# axiom_beta_plugin_module_TE0714_SDI_v0_9.net
KiCad netlist of a schematic drawn in EAGLE
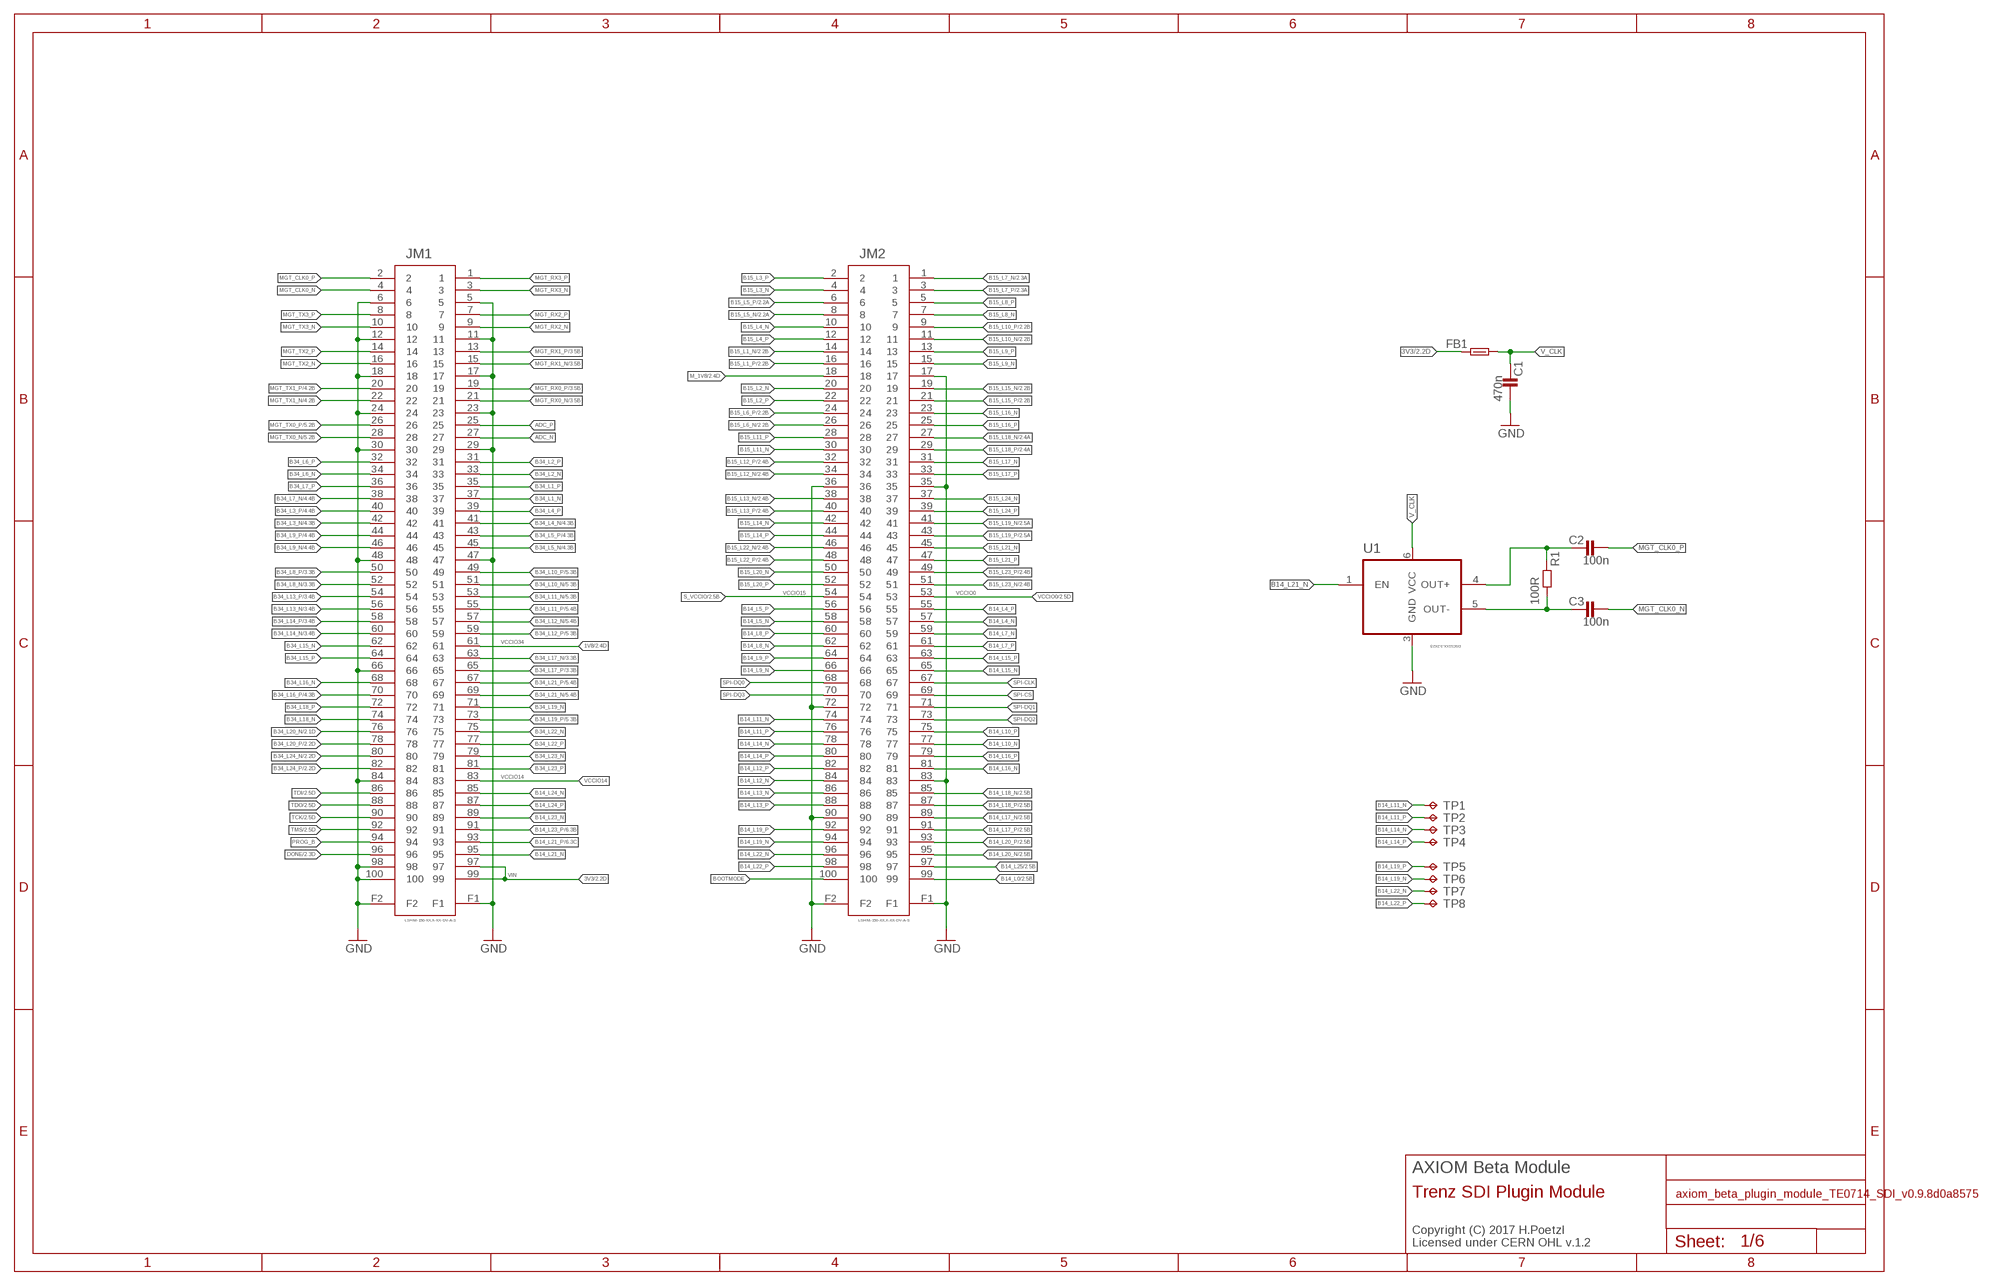
[diagram p0: schematic, sheet 1]
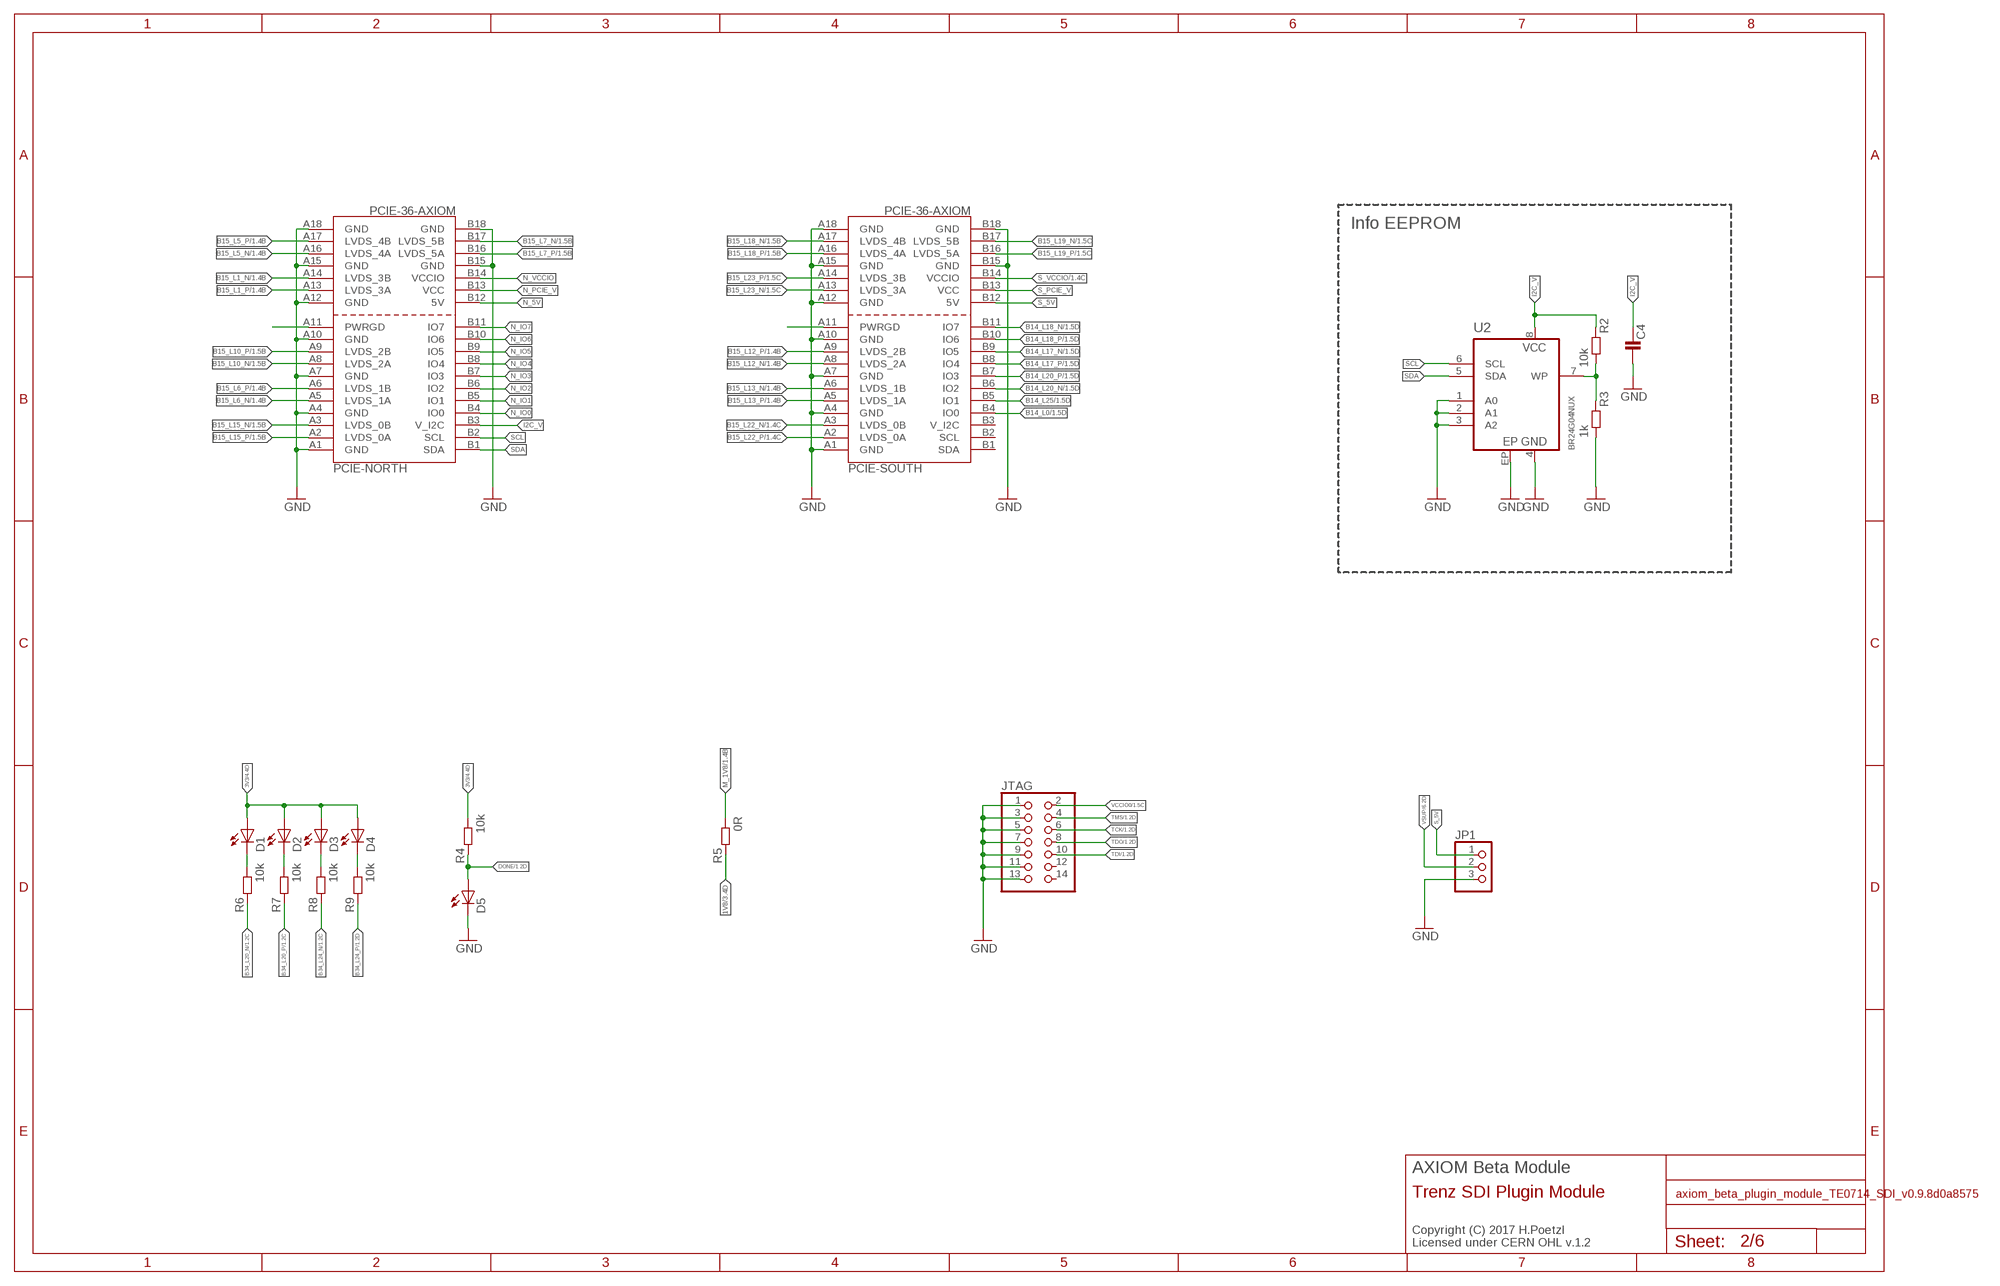
[diagram p1: schematic, sheet 2]
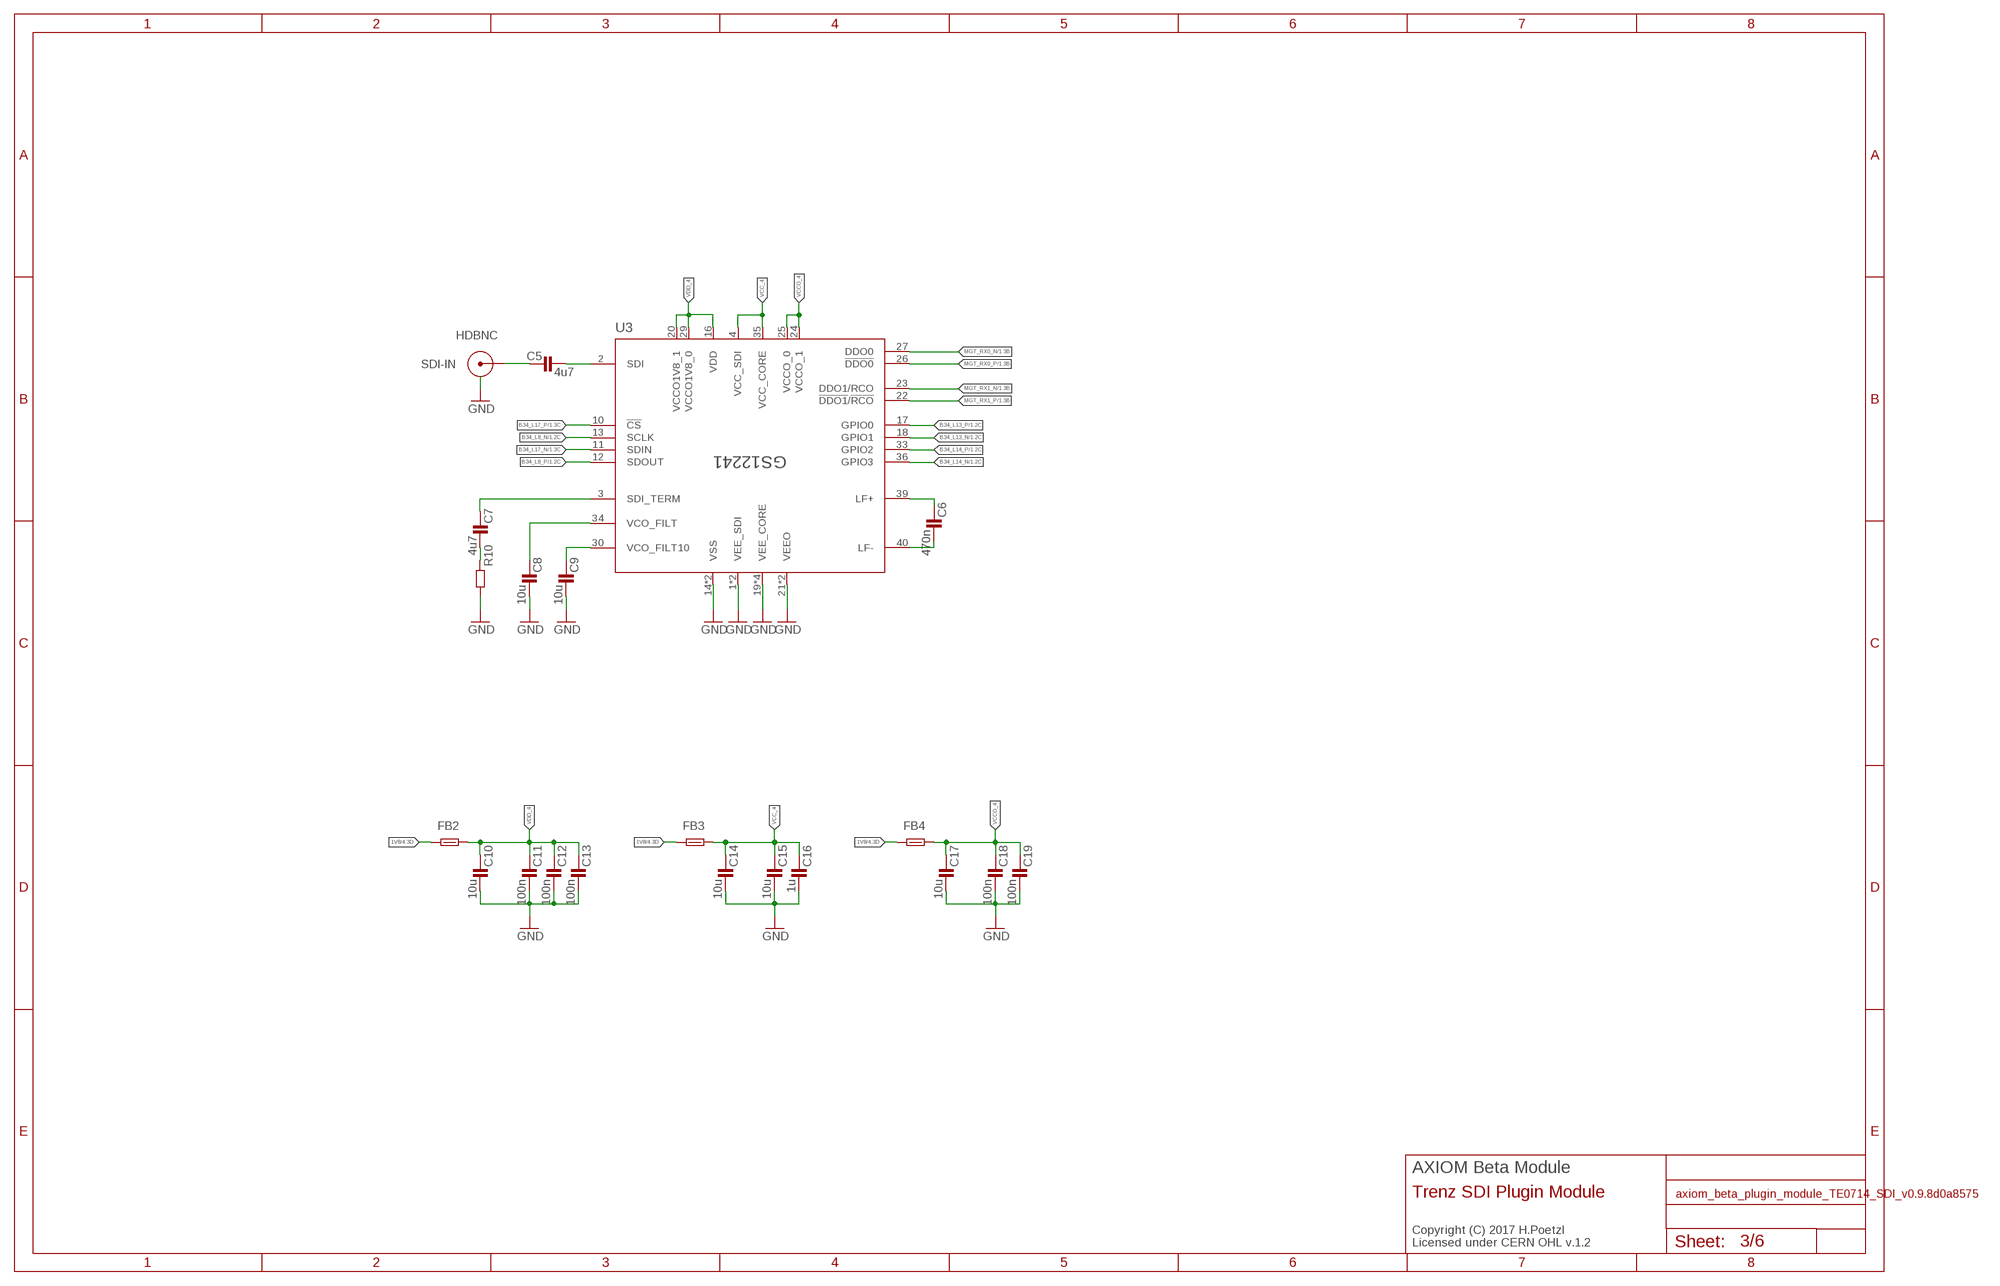
[diagram p2: schematic, sheet 3]
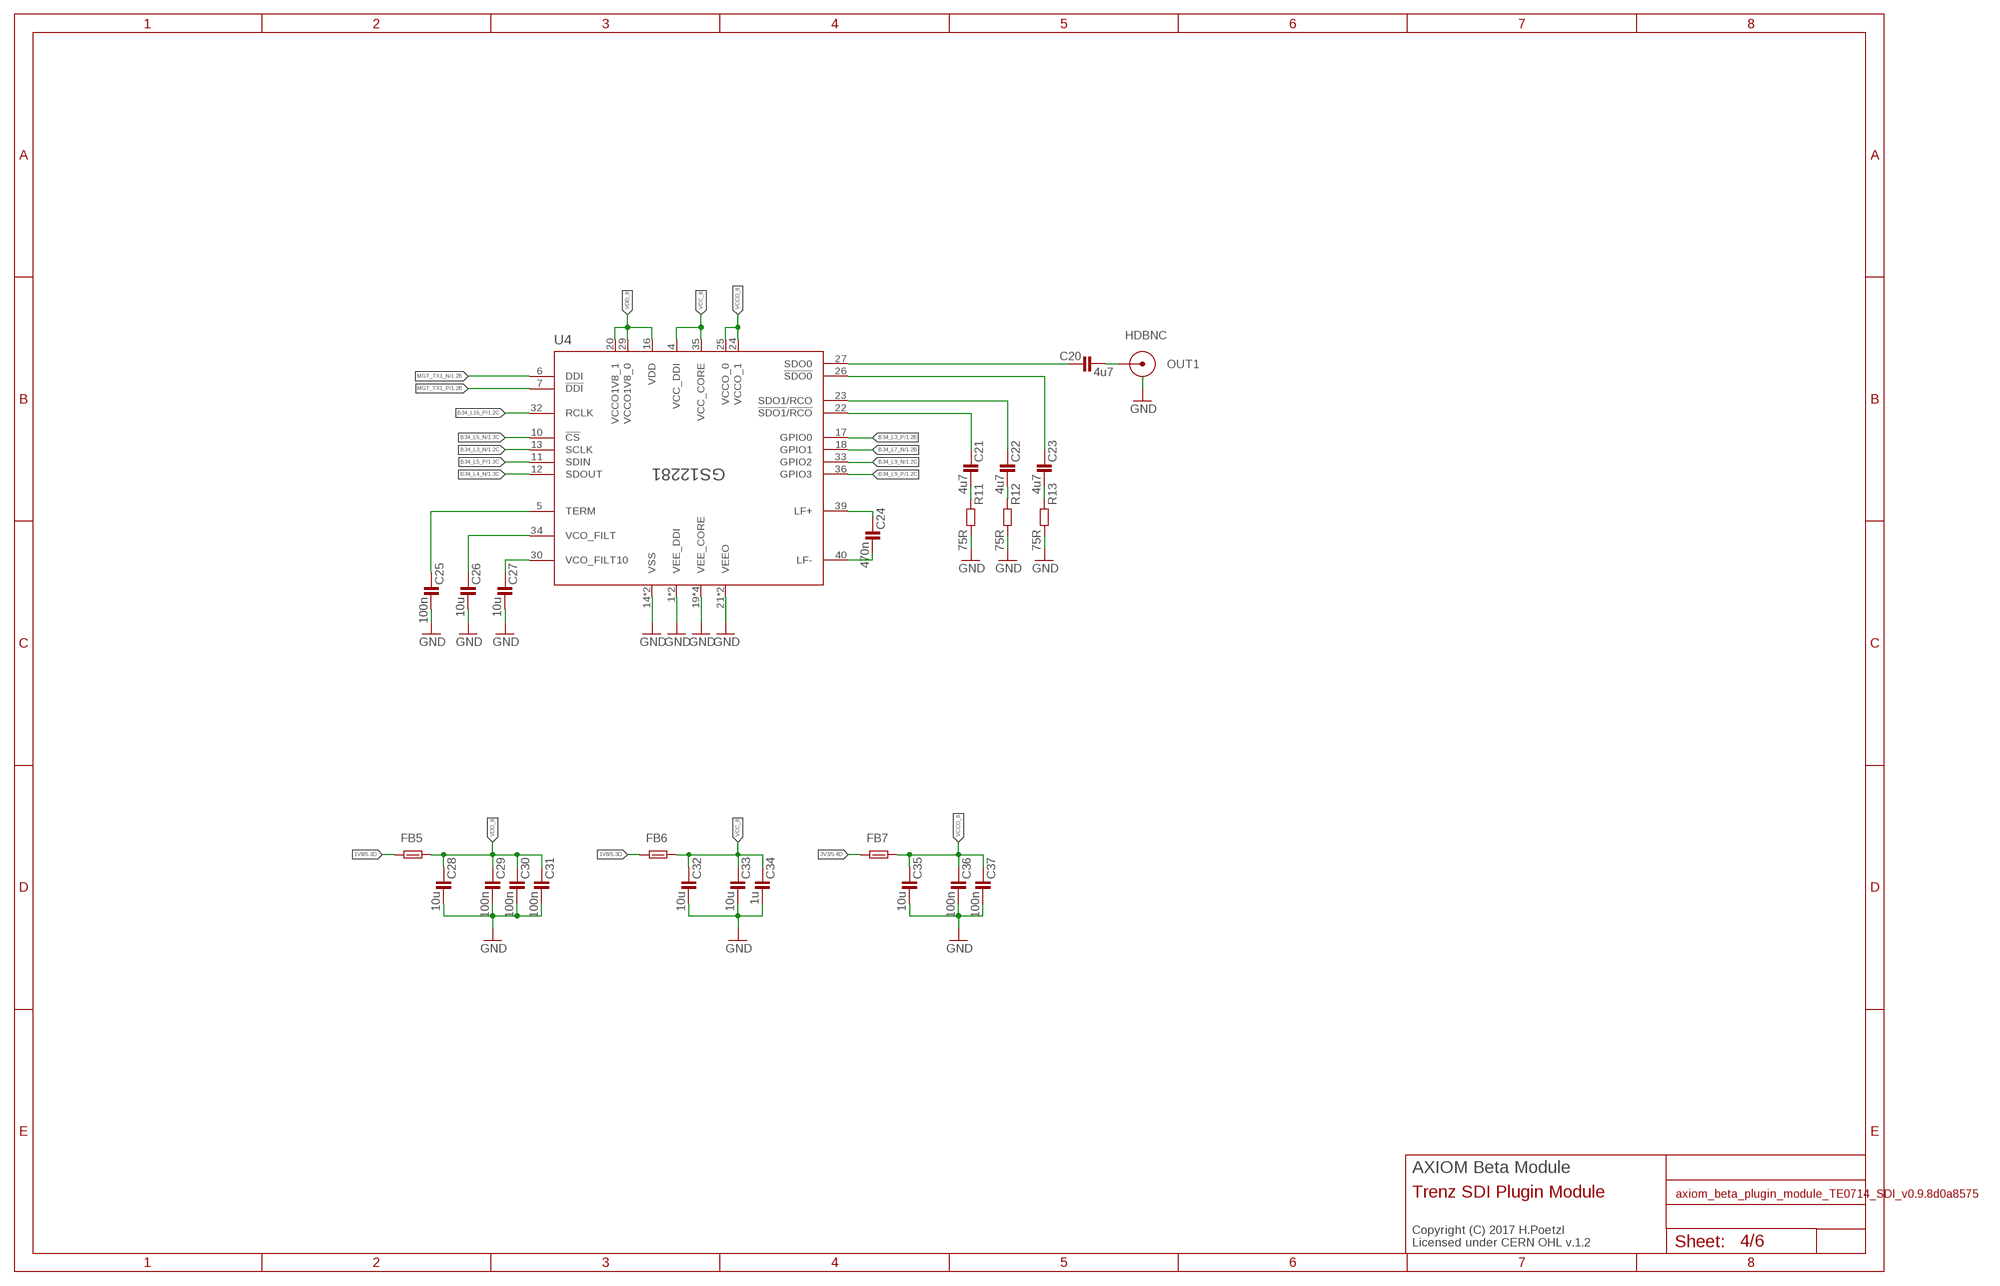
[diagram p3: schematic, sheet 4]
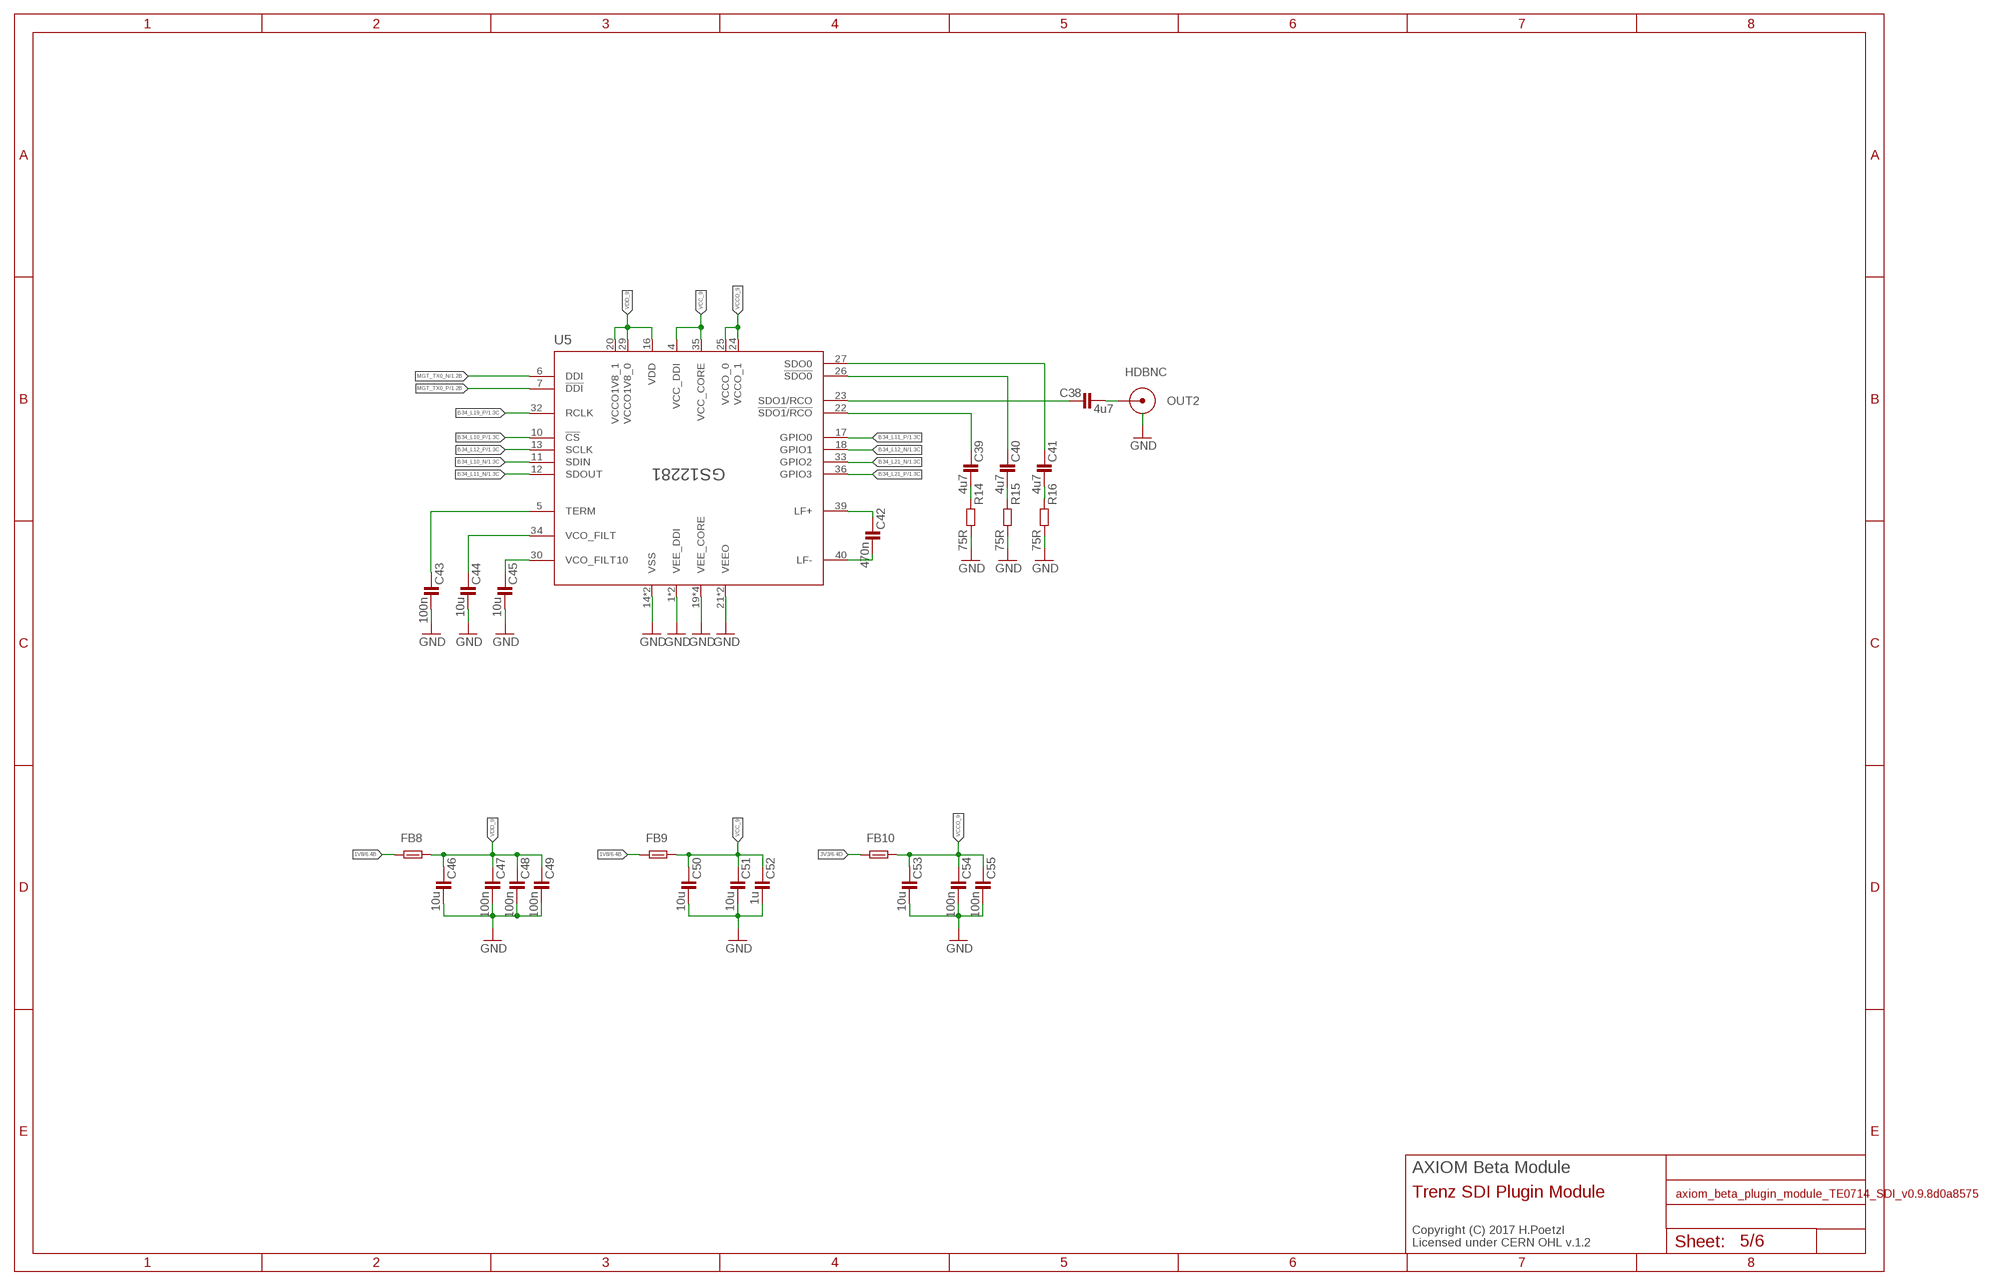
[diagram p4: schematic, sheet 5]
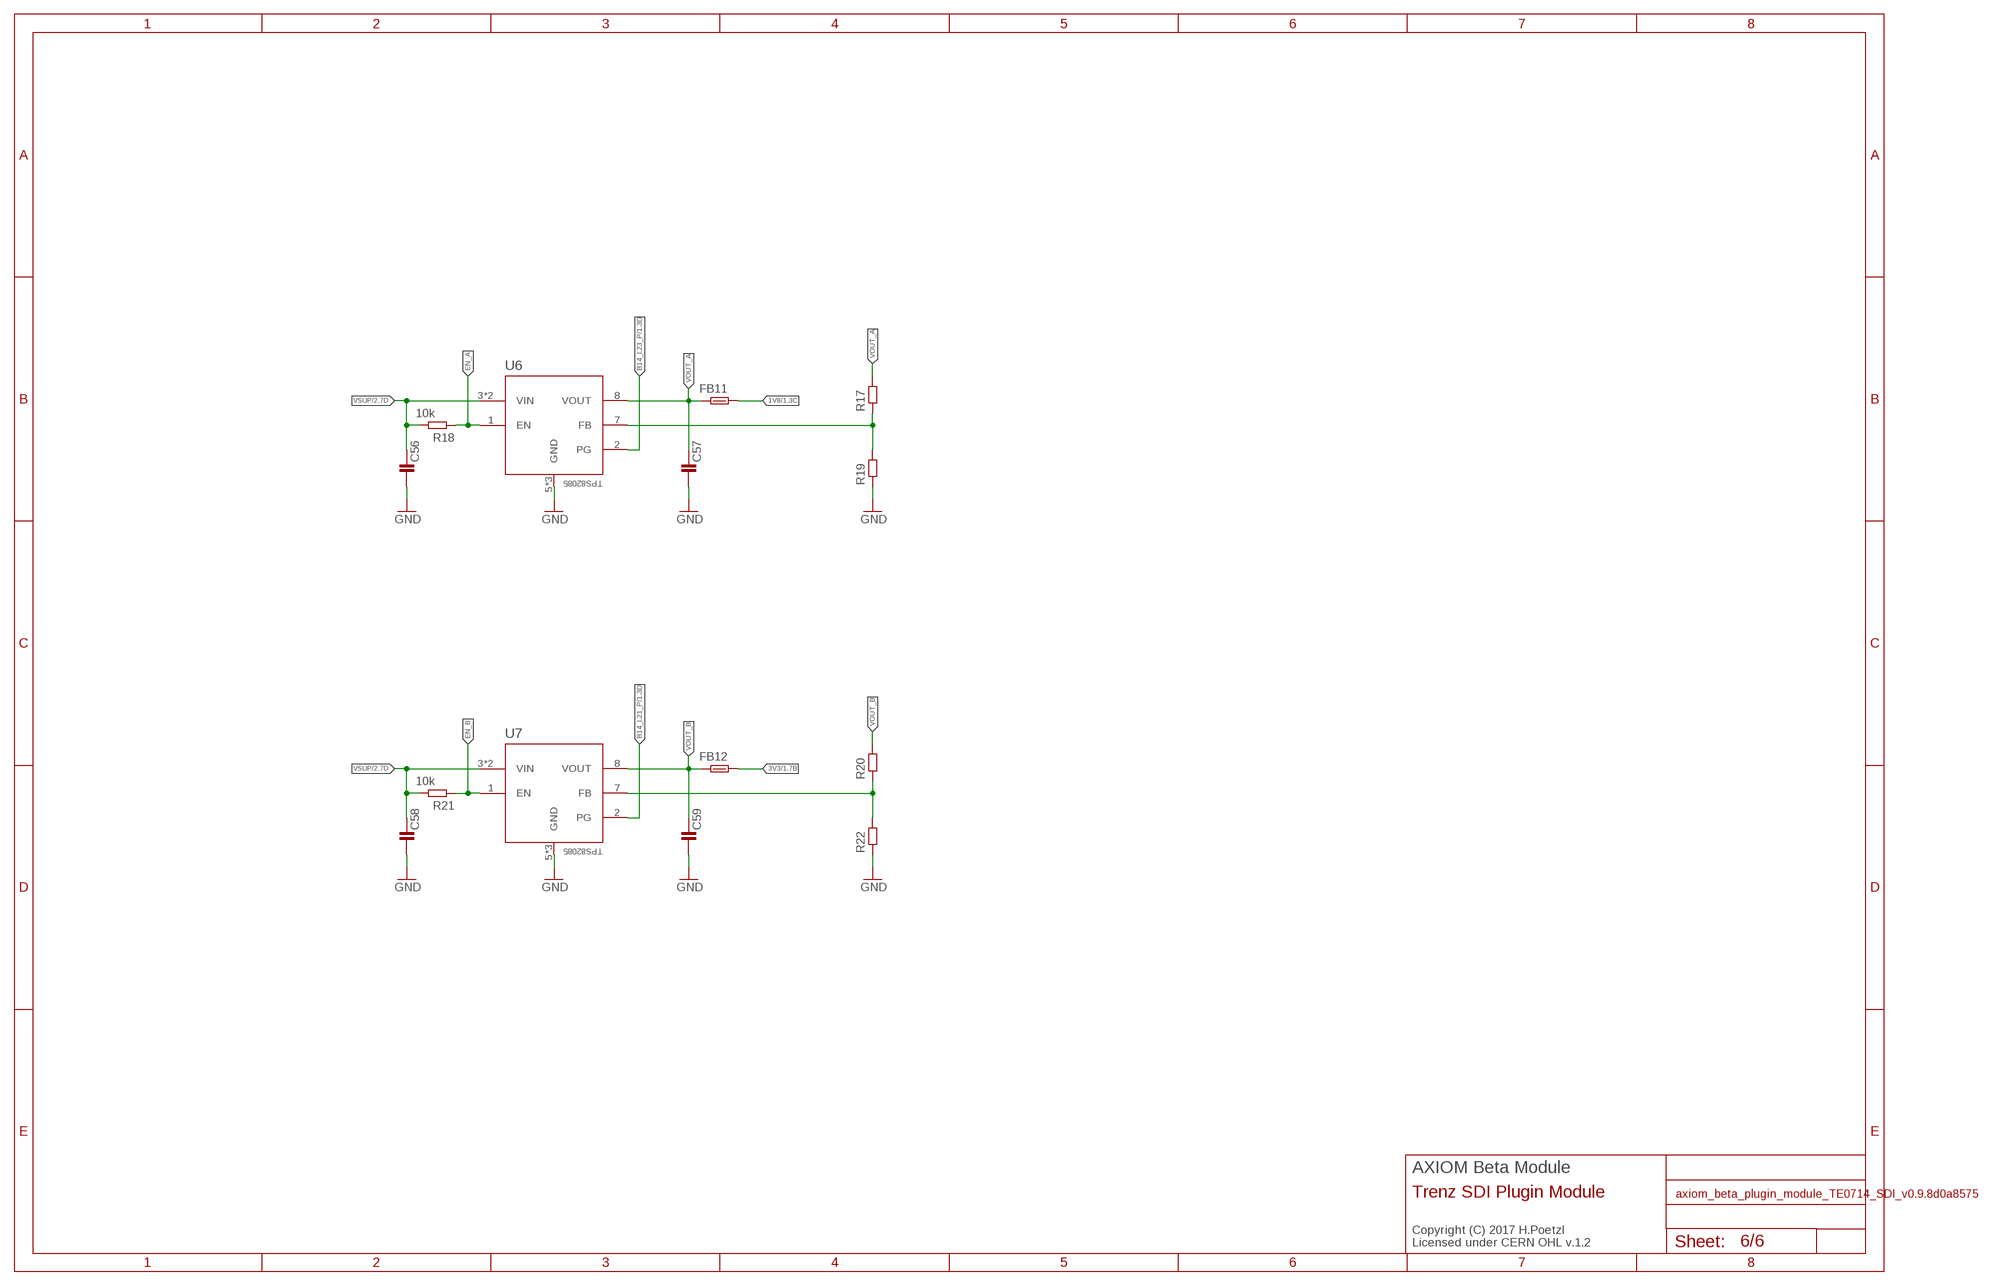
[diagram p5: schematic, sheet 6]

(export (version "E")
  (design (tool "Eeschema 10.0.6"))
  (components
    (comp (ref "C1")
      (value "470n")
      (footprint "eagle-import:0402-C")
      (libsource (lib "eagle-import") (part "C0402-C"))
    )
    (comp (ref "C2")
      (value "100n")
      (footprint "eagle-import:0201-C")
      (libsource (lib "eagle-import") (part "C0201-C"))
    )
    (comp (ref "C3")
      (value "100n")
      (footprint "eagle-import:0201-C")
      (libsource (lib "eagle-import") (part "C0201-C"))
    )
    (comp (ref "FB1")
      (value "FB0402-C")
      (footprint "eagle-import:0402-C")
      (libsource (lib "eagle-import") (part "FB0402-C"))
    )
    (comp (ref "JM1")
      (value "LSHM-150-XX.X-XX-DV-A-S")
      (footprint "eagle-import:LSHM-150-XX.X-XX-DV-A-S")
      (libsource (lib "eagle-import") (part "LSHM-150-XX.X-XX-DV-A-S"))
    )
    (comp (ref "JM2")
      (value "LSHM-150-XX.X-XX-DV-A-S")
      (footprint "eagle-import:LSHM-150-XX.X-XX-DV-A-S")
      (libsource (lib "eagle-import") (part "LSHM-150-XX.X-XX-DV-A-S"))
    )
    (comp (ref "R1")
      (value "100R")
      (footprint "eagle-import:0201-C")
      (libsource (lib "eagle-import") (part "R0201-C"))
    )
    (comp (ref "TP1")
      (value "TPTP08R")
      (footprint "eagle-import:TP08R")
      (libsource (lib "eagle-import") (part "TPTP08R"))
    )
    (comp (ref "TP2")
      (value "TPTP08R")
      (footprint "eagle-import:TP08R")
      (libsource (lib "eagle-import") (part "TPTP08R"))
    )
    (comp (ref "TP3")
      (value "TPTP08R")
      (footprint "eagle-import:TP08R")
      (libsource (lib "eagle-import") (part "TPTP08R"))
    )
    (comp (ref "TP4")
      (value "TPTP08R")
      (footprint "eagle-import:TP08R")
      (libsource (lib "eagle-import") (part "TPTP08R"))
    )
    (comp (ref "TP5")
      (value "TPTP10R")
      (footprint "eagle-import:TP10R")
      (libsource (lib "eagle-import") (part "TPTP10R"))
    )
    (comp (ref "TP6")
      (value "TPTP10R")
      (footprint "eagle-import:TP10R")
      (libsource (lib "eagle-import") (part "TPTP10R"))
    )
    (comp (ref "TP7")
      (value "TPTP10R")
      (footprint "eagle-import:TP10R")
      (libsource (lib "eagle-import") (part "TPTP10R"))
    )
    (comp (ref "TP8")
      (value "TPTP10R")
      (footprint "eagle-import:TP10R")
      (libsource (lib "eagle-import") (part "TPTP10R"))
    )
    (comp (ref "U1")
      (value "DSC11XX-3.2X2.5")
      (footprint "eagle-import:3.2X2.5")
      (libsource (lib "eagle-import") (part "DSC11XX-3.2X2.5"))
    )
    (comp (ref "C20")
      (value "4u7")
      (footprint "eagle-import:0402-C")
      (libsource (lib "eagle-import") (part "C0402-C"))
    )
    (comp (ref "C21")
      (value "4u7")
      (footprint "eagle-import:0402-C")
      (libsource (lib "eagle-import") (part "C0402-C"))
    )
    (comp (ref "C22")
      (value "4u7")
      (footprint "eagle-import:0402-C")
      (libsource (lib "eagle-import") (part "C0402-C"))
    )
    (comp (ref "C23")
      (value "4u7")
      (footprint "eagle-import:0402-C")
      (libsource (lib "eagle-import") (part "C0402-C"))
    )
    (comp (ref "C24")
      (value "470n")
      (footprint "eagle-import:0201-C")
      (libsource (lib "eagle-import") (part "C0201-C"))
    )
    (comp (ref "C25")
      (value "100n")
      (footprint "eagle-import:0201-C")
      (libsource (lib "eagle-import") (part "C0201-C"))
    )
    (comp (ref "C26")
      (value "10u")
      (footprint "eagle-import:0201-C")
      (libsource (lib "eagle-import") (part "C0201-C"))
    )
    (comp (ref "C27")
      (value "10u")
      (footprint "eagle-import:0402-C")
      (libsource (lib "eagle-import") (part "C0402-C"))
    )
    (comp (ref "C28")
      (value "10u")
      (footprint "eagle-import:0402-C")
      (libsource (lib "eagle-import") (part "C0402-C"))
    )
    (comp (ref "C29")
      (value "100n")
      (footprint "eagle-import:0201-C")
      (libsource (lib "eagle-import") (part "C0201-C"))
    )
    (comp (ref "C30")
      (value "100n")
      (footprint "eagle-import:0201-C")
      (libsource (lib "eagle-import") (part "C0201-C"))
    )
    (comp (ref "C31")
      (value "100n")
      (footprint "eagle-import:0201-C")
      (libsource (lib "eagle-import") (part "C0201-C"))
    )
    (comp (ref "C32")
      (value "10u")
      (footprint "eagle-import:0402-C")
      (libsource (lib "eagle-import") (part "C0402-C"))
    )
    (comp (ref "C33")
      (value "10u")
      (footprint "eagle-import:0402-C")
      (libsource (lib "eagle-import") (part "C0402-C"))
    )
    (comp (ref "C34")
      (value "1u")
      (footprint "eagle-import:0201-C")
      (libsource (lib "eagle-import") (part "C0201-C"))
    )
    (comp (ref "C35")
      (value "10u")
      (footprint "eagle-import:0402-C")
      (libsource (lib "eagle-import") (part "C0402-C"))
    )
    (comp (ref "C36")
      (value "100n")
      (footprint "eagle-import:0201-C")
      (libsource (lib "eagle-import") (part "C0201-C"))
    )
    (comp (ref "C37")
      (value "100n")
      (footprint "eagle-import:0201-C")
      (libsource (lib "eagle-import") (part "C0201-C"))
    )
    (comp (ref "FB5")
      (value "FB0402-C")
      (footprint "eagle-import:0402-C")
      (libsource (lib "eagle-import") (part "FB0402-C"))
    )
    (comp (ref "FB6")
      (value "FB0402-C")
      (footprint "eagle-import:0402-C")
      (libsource (lib "eagle-import") (part "FB0402-C"))
    )
    (comp (ref "FB7")
      (value "FB0402-C")
      (footprint "eagle-import:0402-C")
      (libsource (lib "eagle-import") (part "FB0402-C"))
    )
    (comp (ref "OUT1")
      (value "HDBNC")
      (footprint "eagle-import:HDBNC_EDGE_2SIDE")
      (libsource (lib "eagle-import") (part "HDBNC"))
    )
    (comp (ref "R11")
      (value "75R")
      (footprint "eagle-import:0201-C")
      (libsource (lib "eagle-import") (part "R0201-C"))
    )
    (comp (ref "R12")
      (value "75R")
      (footprint "eagle-import:0201-C")
      (libsource (lib "eagle-import") (part "R0201-C"))
    )
    (comp (ref "R13")
      (value "75R")
      (footprint "eagle-import:0201-C")
      (libsource (lib "eagle-import") (part "R0201-C"))
    )
    (comp (ref "U4")
      (value "GS12281")
      (footprint "eagle-import:UQFN40P600X400X100-41N")
      (libsource (lib "eagle-import") (part "GS12281"))
    )
    (comp (ref "C4")
      (value "C0402-B")
      (footprint "eagle-import:0402-B")
      (libsource (lib "eagle-import") (part "C0402-B"))
    )
    (comp (ref "D1")
      (value "LED")
      (footprint "eagle-import:CHIPLED_0603")
      (libsource (lib "eagle-import") (part "LED"))
    )
    (comp (ref "D2")
      (value "LED")
      (footprint "eagle-import:CHIPLED_0603")
      (libsource (lib "eagle-import") (part "LED"))
    )
    (comp (ref "D3")
      (value "LED")
      (footprint "eagle-import:CHIPLED_0603")
      (libsource (lib "eagle-import") (part "LED"))
    )
    (comp (ref "D4")
      (value "LED")
      (footprint "eagle-import:CHIPLED_0603")
      (libsource (lib "eagle-import") (part "LED"))
    )
    (comp (ref "D5")
      (value "LED")
      (footprint "eagle-import:CHIPLED_0603")
      (libsource (lib "eagle-import") (part "LED"))
    )
    (comp (ref "JP1")
      (value "PINHD-1X03_2.54-90°-S")
      (footprint "eagle-import:1X03_90-S")
      (libsource (lib "eagle-import") (part "PINHD-1X03_2.54-90°-S"))
    )
    (comp (ref "JTAG")
      (value "PINHD-2X07_2.00")
      (footprint "eagle-import:2X07M")
      (libsource (lib "eagle-import") (part "PINHD-2X07_2.00"))
    )
    (comp (ref "PCIE-NORTH")
      (value "PCIE-36-AXIOM")
      (footprint "eagle-import:PCIE-36-AXIOM")
      (libsource (lib "eagle-import") (part "PCIE-36-AXIOM"))
    )
    (comp (ref "PCIE-SOUTH")
      (value "PCIE-36-AXIOM")
      (footprint "eagle-import:PCIE-36-AXIOM")
      (libsource (lib "eagle-import") (part "PCIE-36-AXIOM"))
    )
    (comp (ref "R2")
      (value "10k")
      (footprint "eagle-import:0402-B")
      (libsource (lib "eagle-import") (part "R0402-B"))
    )
    (comp (ref "R3")
      (value "1k")
      (footprint "eagle-import:0402-B")
      (libsource (lib "eagle-import") (part "R0402-B"))
    )
    (comp (ref "R4")
      (value "10k")
      (footprint "eagle-import:0402-C")
      (libsource (lib "eagle-import") (part "R0402-C"))
    )
    (comp (ref "R5")
      (value "0R")
      (footprint "eagle-import:0402-C")
      (libsource (lib "eagle-import") (part "R0402-C"))
    )
    (comp (ref "R6")
      (value "10k")
      (footprint "eagle-import:0402-C")
      (libsource (lib "eagle-import") (part "R0402-C"))
    )
    (comp (ref "R7")
      (value "10k")
      (footprint "eagle-import:0402-C")
      (libsource (lib "eagle-import") (part "R0402-C"))
    )
    (comp (ref "R8")
      (value "10k")
      (footprint "eagle-import:0402-C")
      (libsource (lib "eagle-import") (part "R0402-C"))
    )
    (comp (ref "R9")
      (value "10k")
      (footprint "eagle-import:0402-C")
      (libsource (lib "eagle-import") (part "R0402-C"))
    )
    (comp (ref "U2")
      (value "BR24G04NUX")
      (footprint "eagle-import:DFN200X300X100-9N")
      (libsource (lib "eagle-import") (part "BR24G04NUX"))
    )
    (comp (ref "C5")
      (value "4u7")
      (footprint "eagle-import:0402-C")
      (libsource (lib "eagle-import") (part "C0402-C"))
    )
    (comp (ref "C6")
      (value "470n")
      (footprint "eagle-import:0201-C")
      (libsource (lib "eagle-import") (part "C0201-C"))
    )
    (comp (ref "C7")
      (value "4u7")
      (footprint "eagle-import:0402-C")
      (libsource (lib "eagle-import") (part "C0402-C"))
    )
    (comp (ref "C8")
      (value "10u")
      (footprint "eagle-import:0201-C")
      (libsource (lib "eagle-import") (part "C0201-C"))
    )
    (comp (ref "C9")
      (value "10u")
      (footprint "eagle-import:0402-C")
      (libsource (lib "eagle-import") (part "C0402-C"))
    )
    (comp (ref "C10")
      (value "10u")
      (footprint "eagle-import:0402-C")
      (libsource (lib "eagle-import") (part "C0402-C"))
    )
    (comp (ref "C11")
      (value "100n")
      (footprint "eagle-import:0201-C")
      (libsource (lib "eagle-import") (part "C0201-C"))
    )
    (comp (ref "C12")
      (value "100n")
      (footprint "eagle-import:0201-C")
      (libsource (lib "eagle-import") (part "C0201-C"))
    )
    (comp (ref "C13")
      (value "100n")
      (footprint "eagle-import:0201-C")
      (libsource (lib "eagle-import") (part "C0201-C"))
    )
    (comp (ref "C14")
      (value "10u")
      (footprint "eagle-import:0402-C")
      (libsource (lib "eagle-import") (part "C0402-C"))
    )
    (comp (ref "C15")
      (value "10u")
      (footprint "eagle-import:0402-C")
      (libsource (lib "eagle-import") (part "C0402-C"))
    )
    (comp (ref "C16")
      (value "1u")
      (footprint "eagle-import:0201-C")
      (libsource (lib "eagle-import") (part "C0201-C"))
    )
    (comp (ref "C17")
      (value "10u")
      (footprint "eagle-import:0402-C")
      (libsource (lib "eagle-import") (part "C0402-C"))
    )
    (comp (ref "C18")
      (value "100n")
      (footprint "eagle-import:0201-C")
      (libsource (lib "eagle-import") (part "C0201-C"))
    )
    (comp (ref "C19")
      (value "100n")
      (footprint "eagle-import:0201-C")
      (libsource (lib "eagle-import") (part "C0201-C"))
    )
    (comp (ref "FB2")
      (value "FB0402-C")
      (footprint "eagle-import:0402-C")
      (libsource (lib "eagle-import") (part "FB0402-C"))
    )
    (comp (ref "FB3")
      (value "FB0402-C")
      (footprint "eagle-import:0402-C")
      (libsource (lib "eagle-import") (part "FB0402-C"))
    )
    (comp (ref "FB4")
      (value "FB0402-C")
      (footprint "eagle-import:0402-C")
      (libsource (lib "eagle-import") (part "FB0402-C"))
    )
    (comp (ref "R10")
      (value "R0201-C")
      (footprint "eagle-import:0201-C")
      (libsource (lib "eagle-import") (part "R0201-C"))
    )
    (comp (ref "SDI-IN")
      (value "HDBNC")
      (footprint "eagle-import:HDBNC_EDGE_2SIDE")
      (libsource (lib "eagle-import") (part "HDBNC"))
    )
    (comp (ref "U3")
      (value "GS12241")
      (footprint "eagle-import:UQFN40P600X400X100-41N")
      (libsource (lib "eagle-import") (part "GS12241"))
    )
    (comp (ref "C38")
      (value "4u7")
      (footprint "eagle-import:0402-C")
      (libsource (lib "eagle-import") (part "C0402-C"))
    )
    (comp (ref "C39")
      (value "4u7")
      (footprint "eagle-import:0402-C")
      (libsource (lib "eagle-import") (part "C0402-C"))
    )
    (comp (ref "C40")
      (value "4u7")
      (footprint "eagle-import:0402-C")
      (libsource (lib "eagle-import") (part "C0402-C"))
    )
    (comp (ref "C41")
      (value "4u7")
      (footprint "eagle-import:0402-C")
      (libsource (lib "eagle-import") (part "C0402-C"))
    )
    (comp (ref "C42")
      (value "470n")
      (footprint "eagle-import:0201-C")
      (libsource (lib "eagle-import") (part "C0201-C"))
    )
    (comp (ref "C43")
      (value "100n")
      (footprint "eagle-import:0201-C")
      (libsource (lib "eagle-import") (part "C0201-C"))
    )
    (comp (ref "C44")
      (value "10u")
      (footprint "eagle-import:0402-C")
      (libsource (lib "eagle-import") (part "C0402-C"))
    )
    (comp (ref "C45")
      (value "10u")
      (footprint "eagle-import:0402-C")
      (libsource (lib "eagle-import") (part "C0402-C"))
    )
    (comp (ref "C46")
      (value "10u")
      (footprint "eagle-import:0402-C")
      (libsource (lib "eagle-import") (part "C0402-C"))
    )
    (comp (ref "C47")
      (value "100n")
      (footprint "eagle-import:0201-C")
      (libsource (lib "eagle-import") (part "C0201-C"))
    )
    (comp (ref "C48")
      (value "100n")
      (footprint "eagle-import:0201-C")
      (libsource (lib "eagle-import") (part "C0201-C"))
    )
    (comp (ref "C49")
      (value "100n")
      (footprint "eagle-import:0201-C")
      (libsource (lib "eagle-import") (part "C0201-C"))
    )
    (comp (ref "C50")
      (value "10u")
      (footprint "eagle-import:0402-C")
      (libsource (lib "eagle-import") (part "C0402-C"))
    )
    (comp (ref "C51")
      (value "10u")
      (footprint "eagle-import:0402-C")
      (libsource (lib "eagle-import") (part "C0402-C"))
    )
    (comp (ref "C52")
      (value "1u")
      (footprint "eagle-import:0201-C")
      (libsource (lib "eagle-import") (part "C0201-C"))
    )
    (comp (ref "C53")
      (value "10u")
      (footprint "eagle-import:0402-C")
      (libsource (lib "eagle-import") (part "C0402-C"))
    )
    (comp (ref "C54")
      (value "100n")
      (footprint "eagle-import:0201-C")
      (libsource (lib "eagle-import") (part "C0201-C"))
    )
    (comp (ref "C55")
      (value "100n")
      (footprint "eagle-import:0201-C")
      (libsource (lib "eagle-import") (part "C0201-C"))
    )
    (comp (ref "FB8")
      (value "FB0402-C")
      (footprint "eagle-import:0402-C")
      (libsource (lib "eagle-import") (part "FB0402-C"))
    )
    (comp (ref "FB9")
      (value "FB0402-C")
      (footprint "eagle-import:0402-C")
      (libsource (lib "eagle-import") (part "FB0402-C"))
    )
    (comp (ref "FB10")
      (value "FB0402-C")
      (footprint "eagle-import:0402-C")
      (libsource (lib "eagle-import") (part "FB0402-C"))
    )
    (comp (ref "OUT2")
      (value "HDBNC")
      (footprint "eagle-import:HDBNC_EDGE_2SIDE")
      (libsource (lib "eagle-import") (part "HDBNC"))
    )
    (comp (ref "R14")
      (value "75R")
      (footprint "eagle-import:0201-C")
      (libsource (lib "eagle-import") (part "R0201-C"))
    )
    (comp (ref "R15")
      (value "75R")
      (footprint "eagle-import:0201-C")
      (libsource (lib "eagle-import") (part "R0201-C"))
    )
    (comp (ref "R16")
      (value "75R")
      (footprint "eagle-import:0201-C")
      (libsource (lib "eagle-import") (part "R0201-C"))
    )
    (comp (ref "U5")
      (value "GS12281")
      (footprint "eagle-import:UQFN40P600X400X100-41N")
      (libsource (lib "eagle-import") (part "GS12281"))
    )
    (comp (ref "C56")
      (value "C0603-C")
      (footprint "eagle-import:0603-C")
      (libsource (lib "eagle-import") (part "C0603-C"))
    )
    (comp (ref "C57")
      (value "C0603-C")
      (footprint "eagle-import:0603-C")
      (libsource (lib "eagle-import") (part "C0603-C"))
    )
    (comp (ref "C58")
      (value "C0603-C")
      (footprint "eagle-import:0603-C")
      (libsource (lib "eagle-import") (part "C0603-C"))
    )
    (comp (ref "C59")
      (value "C0603-C")
      (footprint "eagle-import:0603-C")
      (libsource (lib "eagle-import") (part "C0603-C"))
    )
    (comp (ref "FB11")
      (value "FB0603-C")
      (footprint "eagle-import:0603-C")
      (libsource (lib "eagle-import") (part "FB0603-C"))
    )
    (comp (ref "FB12")
      (value "FB0603-C")
      (footprint "eagle-import:0603-C")
      (libsource (lib "eagle-import") (part "FB0603-C"))
    )
    (comp (ref "R17")
      (value "R0201-C")
      (footprint "eagle-import:0201-C")
      (libsource (lib "eagle-import") (part "R0201-C"))
    )
    (comp (ref "R18")
      (value "10k")
      (footprint "eagle-import:0201-C")
      (libsource (lib "eagle-import") (part "R0201-C"))
    )
    (comp (ref "R19")
      (value "R0201-C")
      (footprint "eagle-import:0201-C")
      (libsource (lib "eagle-import") (part "R0201-C"))
    )
    (comp (ref "R20")
      (value "R0201-C")
      (footprint "eagle-import:0201-C")
      (libsource (lib "eagle-import") (part "R0201-C"))
    )
    (comp (ref "R21")
      (value "10k")
      (footprint "eagle-import:0201-C")
      (libsource (lib "eagle-import") (part "R0201-C"))
    )
    (comp (ref "R22")
      (value "R0201-C")
      (footprint "eagle-import:0201-C")
      (libsource (lib "eagle-import") (part "R0201-C"))
    )
    (comp (ref "U6")
      (value "TPS82085")
      (footprint "eagle-import:MICROSIP")
      (libsource (lib "eagle-import") (part "TPS82085"))
    )
    (comp (ref "U7")
      (value "TPS82085")
      (footprint "eagle-import:MICROSIP")
      (libsource (lib "eagle-import") (part "TPS82085"))
    )
  )
  (nets
    (net (code "1") (name "1V8") (class "Default")
      (node (ref "FB11") (pin "2") (pinfunction "2_2") (pintype "passive"))
      (node (ref "FB2") (pin "1") (pinfunction "1_1") (pintype "passive"))
      (node (ref "FB3") (pin "1") (pinfunction "1_1") (pintype "passive"))
      (node (ref "FB4") (pin "1") (pinfunction "1_1") (pintype "passive"))
      (node (ref "FB5") (pin "1") (pinfunction "1_1") (pintype "passive"))
      (node (ref "FB6") (pin "1") (pinfunction "1_1") (pintype "passive"))
      (node (ref "FB8") (pin "1") (pinfunction "1_1") (pintype "passive"))
      (node (ref "FB9") (pin "1") (pinfunction "1_1") (pintype "passive"))
      (node (ref "JM1") (pin "61") (pinfunction "61_61") (pintype "bidirectional"))
      (node (ref "R5") (pin "1") (pinfunction "1_1") (pintype "passive"))
    )
    (net (code "2") (name "3V3") (class "Default")
      (node (ref "D1") (pin "A") (pinfunction "A_A") (pintype "passive"))
      (node (ref "D2") (pin "A") (pinfunction "A_A") (pintype "passive"))
      (node (ref "D3") (pin "A") (pinfunction "A_A") (pintype "passive"))
      (node (ref "D4") (pin "A") (pinfunction "A_A") (pintype "passive"))
      (node (ref "FB1") (pin "1") (pinfunction "1_1") (pintype "passive"))
      (node (ref "FB10") (pin "1") (pinfunction "1_1") (pintype "passive"))
      (node (ref "FB12") (pin "2") (pinfunction "2_2") (pintype "passive"))
      (node (ref "FB7") (pin "1") (pinfunction "1_1") (pintype "passive"))
      (node (ref "JM1") (pin "97") (pinfunction "97_97") (pintype "bidirectional"))
      (node (ref "JM1") (pin "99") (pinfunction "99_99") (pintype "bidirectional"))
      (node (ref "R4") (pin "2") (pinfunction "2_2") (pintype "passive"))
    )
    (net (code "3") (name "ADC_N") (class "Default")
      (node (ref "JM1") (pin "27") (pinfunction "27_27") (pintype "bidirectional"))
    )
    (net (code "4") (name "ADC_P") (class "Default")
      (node (ref "JM1") (pin "25") (pinfunction "25_25") (pintype "bidirectional"))
    )
    (net (code "5") (name "B14_L0") (class "Default")
      (node (ref "JM2") (pin "99") (pinfunction "99_99") (pintype "bidirectional"))
      (node (ref "PCIE-SOUTH") (pin "B4") (pinfunction "IO0_B4") (pintype "passive"))
    )
    (net (code "6") (name "B14_L4_N") (class "Default")
      (node (ref "JM2") (pin "57") (pinfunction "57_57") (pintype "bidirectional"))
    )
    (net (code "7") (name "B14_L4_P") (class "Default")
      (node (ref "JM2") (pin "55") (pinfunction "55_55") (pintype "bidirectional"))
    )
    (net (code "8") (name "B14_L5_N") (class "Default")
      (node (ref "JM2") (pin "58") (pinfunction "58_58") (pintype "bidirectional"))
    )
    (net (code "9") (name "B14_L5_P") (class "Default")
      (node (ref "JM2") (pin "56") (pinfunction "56_56") (pintype "bidirectional"))
    )
    (net (code "10") (name "B14_L7_N") (class "Default")
      (node (ref "JM2") (pin "59") (pinfunction "59_59") (pintype "bidirectional"))
    )
    (net (code "11") (name "B14_L7_P") (class "Default")
      (node (ref "JM2") (pin "61") (pinfunction "61_61") (pintype "bidirectional"))
    )
    (net (code "12") (name "B14_L8_N") (class "Default")
      (node (ref "JM2") (pin "62") (pinfunction "62_62") (pintype "bidirectional"))
    )
    (net (code "13") (name "B14_L8_P") (class "Default")
      (node (ref "JM2") (pin "60") (pinfunction "60_60") (pintype "bidirectional"))
    )
    (net (code "14") (name "B14_L9_N") (class "Default")
      (node (ref "JM2") (pin "66") (pinfunction "66_66") (pintype "bidirectional"))
    )
    (net (code "15") (name "B14_L9_P") (class "Default")
      (node (ref "JM2") (pin "64") (pinfunction "64_64") (pintype "bidirectional"))
    )
    (net (code "16") (name "B14_L10_N") (class "Default")
      (node (ref "JM2") (pin "77") (pinfunction "77_77") (pintype "bidirectional"))
    )
    (net (code "17") (name "B14_L10_P") (class "Default")
      (node (ref "JM2") (pin "75") (pinfunction "75_75") (pintype "bidirectional"))
    )
    (net (code "18") (name "B14_L11_N") (class "Default")
      (node (ref "JM2") (pin "74") (pinfunction "74_74") (pintype "bidirectional"))
      (node (ref "TP1") (pin "TP") (pinfunction "TP_TP") (pintype "input"))
    )
    (net (code "19") (name "B14_L11_P") (class "Default")
      (node (ref "JM2") (pin "76") (pinfunction "76_76") (pintype "bidirectional"))
      (node (ref "TP2") (pin "TP") (pinfunction "TP_TP") (pintype "input"))
    )
    (net (code "20") (name "B14_L12_N") (class "Default")
      (node (ref "JM2") (pin "84") (pinfunction "84_84") (pintype "bidirectional"))
    )
    (net (code "21") (name "B14_L12_P") (class "Default")
      (node (ref "JM2") (pin "82") (pinfunction "82_82") (pintype "bidirectional"))
    )
    (net (code "22") (name "B14_L13_N") (class "Default")
      (node (ref "JM2") (pin "86") (pinfunction "86_86") (pintype "bidirectional"))
    )
    (net (code "23") (name "B14_L13_P") (class "Default")
      (node (ref "JM2") (pin "88") (pinfunction "88_88") (pintype "bidirectional"))
    )
    (net (code "24") (name "B14_L14_N") (class "Default")
      (node (ref "JM2") (pin "78") (pinfunction "78_78") (pintype "bidirectional"))
      (node (ref "TP3") (pin "TP") (pinfunction "TP_TP") (pintype "input"))
    )
    (net (code "25") (name "B14_L14_P") (class "Default")
      (node (ref "JM2") (pin "80") (pinfunction "80_80") (pintype "bidirectional"))
      (node (ref "TP4") (pin "TP") (pinfunction "TP_TP") (pintype "input"))
    )
    (net (code "26") (name "B14_L15_N") (class "Default")
      (node (ref "JM2") (pin "65") (pinfunction "65_65") (pintype "bidirectional"))
    )
    (net (code "27") (name "B14_L15_P") (class "Default")
      (node (ref "JM2") (pin "63") (pinfunction "63_63") (pintype "bidirectional"))
    )
    (net (code "28") (name "B14_L16_N") (class "Default")
      (node (ref "JM2") (pin "81") (pinfunction "81_81") (pintype "bidirectional"))
    )
    (net (code "29") (name "B14_L16_P") (class "Default")
      (node (ref "JM2") (pin "79") (pinfunction "79_79") (pintype "bidirectional"))
    )
    (net (code "30") (name "B14_L17_N") (class "Default")
      (node (ref "JM2") (pin "89") (pinfunction "89_89") (pintype "bidirectional"))
      (node (ref "PCIE-SOUTH") (pin "B9") (pinfunction "IO5_B9") (pintype "passive"))
    )
    (net (code "31") (name "B14_L17_P") (class "Default")
      (node (ref "JM2") (pin "91") (pinfunction "91_91") (pintype "bidirectional"))
      (node (ref "PCIE-SOUTH") (pin "B8") (pinfunction "IO4_B8") (pintype "passive"))
    )
    (net (code "32") (name "B14_L18_N") (class "Default")
      (node (ref "JM2") (pin "85") (pinfunction "85_85") (pintype "bidirectional"))
      (node (ref "PCIE-SOUTH") (pin "B11") (pinfunction "IO7_B11") (pintype "passive"))
    )
    (net (code "33") (name "B14_L18_P") (class "Default")
      (node (ref "JM2") (pin "87") (pinfunction "87_87") (pintype "bidirectional"))
      (node (ref "PCIE-SOUTH") (pin "B10") (pinfunction "IO6_B10") (pintype "passive"))
    )
    (net (code "34") (name "B14_L19_N") (class "Default")
      (node (ref "JM2") (pin "94") (pinfunction "94_94") (pintype "bidirectional"))
      (node (ref "TP6") (pin "TP") (pinfunction "TP_TP") (pintype "input"))
    )
    (net (code "35") (name "B14_L19_P") (class "Default")
      (node (ref "JM2") (pin "92") (pinfunction "92_92") (pintype "bidirectional"))
      (node (ref "TP5") (pin "TP") (pinfunction "TP_TP") (pintype "input"))
    )
    (net (code "36") (name "B14_L20_N") (class "Default")
      (node (ref "JM2") (pin "95") (pinfunction "95_95") (pintype "bidirectional"))
      (node (ref "PCIE-SOUTH") (pin "B6") (pinfunction "IO2_B6") (pintype "passive"))
    )
    (net (code "37") (name "B14_L20_P") (class "Default")
      (node (ref "JM2") (pin "93") (pinfunction "93_93") (pintype "bidirectional"))
      (node (ref "PCIE-SOUTH") (pin "B7") (pinfunction "IO3_B7") (pintype "passive"))
    )
    (net (code "38") (name "B14_L21_N") (class "Default")
      (node (ref "JM1") (pin "95") (pinfunction "95_95") (pintype "bidirectional"))
      (node (ref "U1") (pin "1") (pinfunction "EN_1") (pintype "input"))
    )
    (net (code "39") (name "B14_L21_P") (class "Default")
      (node (ref "JM1") (pin "93") (pinfunction "93_93") (pintype "bidirectional"))
      (node (ref "U7") (pin "2") (pinfunction "PG_2") (pintype "power_in"))
    )
    (net (code "40") (name "B14_L22_N") (class "Default")
      (node (ref "JM2") (pin "96") (pinfunction "96_96") (pintype "bidirectional"))
      (node (ref "TP7") (pin "TP") (pinfunction "TP_TP") (pintype "input"))
    )
    (net (code "41") (name "B14_L22_P") (class "Default")
      (node (ref "JM2") (pin "98") (pinfunction "98_98") (pintype "bidirectional"))
      (node (ref "TP8") (pin "TP") (pinfunction "TP_TP") (pintype "input"))
    )
    (net (code "42") (name "B14_L23_N") (class "Default")
      (node (ref "JM1") (pin "89") (pinfunction "89_89") (pintype "bidirectional"))
    )
    (net (code "43") (name "B14_L23_P") (class "Default")
      (node (ref "JM1") (pin "91") (pinfunction "91_91") (pintype "bidirectional"))
      (node (ref "U6") (pin "2") (pinfunction "PG_2") (pintype "power_in"))
    )
    (net (code "44") (name "B14_L24_N") (class "Default")
      (node (ref "JM1") (pin "85") (pinfunction "85_85") (pintype "bidirectional"))
    )
    (net (code "45") (name "B14_L24_P") (class "Default")
      (node (ref "JM1") (pin "87") (pinfunction "87_87") (pintype "bidirectional"))
    )
    (net (code "46") (name "B14_L25") (class "Default")
      (node (ref "JM2") (pin "97") (pinfunction "97_97") (pintype "bidirectional"))
      (node (ref "PCIE-SOUTH") (pin "B5") (pinfunction "IO1_B5") (pintype "passive"))
    )
    (net (code "47") (name "B15_L1_N") (class "Default")
      (node (ref "JM2") (pin "14") (pinfunction "14_14") (pintype "bidirectional"))
      (node (ref "PCIE-NORTH") (pin "A14") (pinfunction "LVDS_3B_A14") (pintype "passive"))
    )
    (net (code "48") (name "B15_L1_P") (class "Default")
      (node (ref "JM2") (pin "16") (pinfunction "16_16") (pintype "bidirectional"))
      (node (ref "PCIE-NORTH") (pin "A13") (pinfunction "LVDS_3A_A13") (pintype "passive"))
    )
    (net (code "49") (name "B15_L2_N") (class "Default")
      (node (ref "JM2") (pin "20") (pinfunction "20_20") (pintype "bidirectional"))
    )
    (net (code "50") (name "B15_L2_P") (class "Default")
      (node (ref "JM2") (pin "22") (pinfunction "22_22") (pintype "bidirectional"))
    )
    (net (code "51") (name "B15_L3_N") (class "Default")
      (node (ref "JM2") (pin "4") (pinfunction "4_4") (pintype "bidirectional"))
    )
    (net (code "52") (name "B15_L3_P") (class "Default")
      (node (ref "JM2") (pin "2") (pinfunction "2_2") (pintype "bidirectional"))
    )
    (net (code "53") (name "B15_L4_N") (class "Default")
      (node (ref "JM2") (pin "10") (pinfunction "10_10") (pintype "bidirectional"))
    )
    (net (code "54") (name "B15_L4_P") (class "Default")
      (node (ref "JM2") (pin "12") (pinfunction "12_12") (pintype "bidirectional"))
    )
    (net (code "55") (name "B15_L5_N") (class "Default")
      (node (ref "JM2") (pin "8") (pinfunction "8_8") (pintype "bidirectional"))
      (node (ref "PCIE-NORTH") (pin "A16") (pinfunction "LVDS_4A_A16") (pintype "passive"))
    )
    (net (code "56") (name "B15_L5_P") (class "Default")
      (node (ref "JM2") (pin "6") (pinfunction "6_6") (pintype "bidirectional"))
      (node (ref "PCIE-NORTH") (pin "A17") (pinfunction "LVDS_4B_A17") (pintype "passive"))
    )
    (net (code "57") (name "B15_L6_N") (class "Default")
      (node (ref "JM2") (pin "26") (pinfunction "26_26") (pintype "bidirectional"))
      (node (ref "PCIE-NORTH") (pin "A5") (pinfunction "LVDS_1A_A5") (pintype "passive"))
    )
    (net (code "58") (name "B15_L6_P") (class "Default")
      (node (ref "JM2") (pin "24") (pinfunction "24_24") (pintype "bidirectional"))
      (node (ref "PCIE-NORTH") (pin "A6") (pinfunction "LVDS_1B_A6") (pintype "passive"))
    )
    (net (code "59") (name "B15_L7_N") (class "Default")
      (node (ref "JM2") (pin "1") (pinfunction "1_1") (pintype "bidirectional"))
      (node (ref "PCIE-NORTH") (pin "B17") (pinfunction "LVDS_5B_B17") (pintype "passive"))
    )
    (net (code "60") (name "B15_L7_P") (class "Default")
      (node (ref "JM2") (pin "3") (pinfunction "3_3") (pintype "bidirectional"))
      (node (ref "PCIE-NORTH") (pin "B16") (pinfunction "LVDS_5A_B16") (pintype "passive"))
    )
    (net (code "61") (name "B15_L8_N") (class "Default")
      (node (ref "JM2") (pin "7") (pinfunction "7_7") (pintype "bidirectional"))
    )
    (net (code "62") (name "B15_L8_P") (class "Default")
      (node (ref "JM2") (pin "5") (pinfunction "5_5") (pintype "bidirectional"))
    )
    (net (code "63") (name "B15_L9_N") (class "Default")
      (node (ref "JM2") (pin "15") (pinfunction "15_15") (pintype "bidirectional"))
    )
    (net (code "64") (name "B15_L9_P") (class "Default")
      (node (ref "JM2") (pin "13") (pinfunction "13_13") (pintype "bidirectional"))
    )
    (net (code "65") (name "B15_L10_N") (class "Default")
      (node (ref "JM2") (pin "11") (pinfunction "11_11") (pintype "bidirectional"))
      (node (ref "PCIE-NORTH") (pin "A8") (pinfunction "LVDS_2A_A8") (pintype "passive"))
    )
    (net (code "66") (name "B15_L10_P") (class "Default")
      (node (ref "JM2") (pin "9") (pinfunction "9_9") (pintype "bidirectional"))
      (node (ref "PCIE-NORTH") (pin "A9") (pinfunction "LVDS_2B_A9") (pintype "passive"))
    )
    (net (code "67") (name "B15_L11_N") (class "Default")
      (node (ref "JM2") (pin "30") (pinfunction "30_30") (pintype "bidirectional"))
    )
    (net (code "68") (name "B15_L11_P") (class "Default")
      (node (ref "JM2") (pin "28") (pinfunction "28_28") (pintype "bidirectional"))
    )
    (net (code "69") (name "B15_L12_N") (class "Default")
      (node (ref "JM2") (pin "34") (pinfunction "34_34") (pintype "bidirectional"))
      (node (ref "PCIE-SOUTH") (pin "A8") (pinfunction "LVDS_2A_A8") (pintype "passive"))
    )
    (net (code "70") (name "B15_L12_P") (class "Default")
      (node (ref "JM2") (pin "32") (pinfunction "32_32") (pintype "bidirectional"))
      (node (ref "PCIE-SOUTH") (pin "A9") (pinfunction "LVDS_2B_A9") (pintype "passive"))
    )
    (net (code "71") (name "B15_L13_N") (class "Default")
      (node (ref "JM2") (pin "38") (pinfunction "38_38") (pintype "bidirectional"))
      (node (ref "PCIE-SOUTH") (pin "A6") (pinfunction "LVDS_1B_A6") (pintype "passive"))
    )
    (net (code "72") (name "B15_L13_P") (class "Default")
      (node (ref "JM2") (pin "40") (pinfunction "40_40") (pintype "bidirectional"))
      (node (ref "PCIE-SOUTH") (pin "A5") (pinfunction "LVDS_1A_A5") (pintype "passive"))
    )
    (net (code "73") (name "B15_L14_N") (class "Default")
      (node (ref "JM2") (pin "42") (pinfunction "42_42") (pintype "bidirectional"))
    )
    (net (code "74") (name "B15_L14_P") (class "Default")
      (node (ref "JM2") (pin "44") (pinfunction "44_44") (pintype "bidirectional"))
    )
    (net (code "75") (name "B15_L15_N") (class "Default")
      (node (ref "JM2") (pin "19") (pinfunction "19_19") (pintype "bidirectional"))
      (node (ref "PCIE-NORTH") (pin "A3") (pinfunction "LVDS_0B_A3") (pintype "passive"))
    )
    (net (code "76") (name "B15_L15_P") (class "Default")
      (node (ref "JM2") (pin "21") (pinfunction "21_21") (pintype "bidirectional"))
      (node (ref "PCIE-NORTH") (pin "A2") (pinfunction "LVDS_0A_A2") (pintype "passive"))
    )
    (net (code "77") (name "B15_L16_N") (class "Default")
      (node (ref "JM2") (pin "23") (pinfunction "23_23") (pintype "bidirectional"))
    )
    (net (code "78") (name "B15_L16_P") (class "Default")
      (node (ref "JM2") (pin "25") (pinfunction "25_25") (pintype "bidirectional"))
    )
    (net (code "79") (name "B15_L17_N") (class "Default")
      (node (ref "JM2") (pin "31") (pinfunction "31_31") (pintype "bidirectional"))
    )
    (net (code "80") (name "B15_L17_P") (class "Default")
      (node (ref "JM2") (pin "33") (pinfunction "33_33") (pintype "bidirectional"))
    )
    (net (code "81") (name "B15_L18_N") (class "Default")
      (node (ref "JM2") (pin "27") (pinfunction "27_27") (pintype "bidirectional"))
      (node (ref "PCIE-SOUTH") (pin "A17") (pinfunction "LVDS_4B_A17") (pintype "passive"))
    )
    (net (code "82") (name "B15_L18_P") (class "Default")
      (node (ref "JM2") (pin "29") (pinfunction "29_29") (pintype "bidirectional"))
      (node (ref "PCIE-SOUTH") (pin "A16") (pinfunction "LVDS_4A_A16") (pintype "passive"))
    )
    (net (code "83") (name "B15_L19_N") (class "Default")
      (node (ref "JM2") (pin "41") (pinfunction "41_41") (pintype "bidirectional"))
      (node (ref "PCIE-SOUTH") (pin "B17") (pinfunction "LVDS_5B_B17") (pintype "passive"))
    )
    (net (code "84") (name "B15_L19_P") (class "Default")
      (node (ref "JM2") (pin "43") (pinfunction "43_43") (pintype "bidirectional"))
      (node (ref "PCIE-SOUTH") (pin "B16") (pinfunction "LVDS_5A_B16") (pintype "passive"))
    )
    (net (code "85") (name "B15_L20_N") (class "Default")
      (node (ref "JM2") (pin "50") (pinfunction "50_50") (pintype "bidirectional"))
    )
    (net (code "86") (name "B15_L20_P") (class "Default")
      (node (ref "JM2") (pin "52") (pinfunction "52_52") (pintype "bidirectional"))
    )
    (net (code "87") (name "B15_L21_N") (class "Default")
      (node (ref "JM2") (pin "45") (pinfunction "45_45") (pintype "bidirectional"))
    )
    (net (code "88") (name "B15_L21_P") (class "Default")
      (node (ref "JM2") (pin "47") (pinfunction "47_47") (pintype "bidirectional"))
    )
    (net (code "89") (name "B15_L22_N") (class "Default")
      (node (ref "JM2") (pin "46") (pinfunction "46_46") (pintype "bidirectional"))
      (node (ref "PCIE-SOUTH") (pin "A3") (pinfunction "LVDS_0B_A3") (pintype "passive"))
    )
    (net (code "90") (name "B15_L22_P") (class "Default")
      (node (ref "JM2") (pin "48") (pinfunction "48_48") (pintype "bidirectional"))
      (node (ref "PCIE-SOUTH") (pin "A2") (pinfunction "LVDS_0A_A2") (pintype "passive"))
    )
    (net (code "91") (name "B15_L23_N") (class "Default")
      (node (ref "JM2") (pin "51") (pinfunction "51_51") (pintype "bidirectional"))
      (node (ref "PCIE-SOUTH") (pin "A13") (pinfunction "LVDS_3A_A13") (pintype "passive"))
    )
    (net (code "92") (name "B15_L23_P") (class "Default")
      (node (ref "JM2") (pin "49") (pinfunction "49_49") (pintype "bidirectional"))
      (node (ref "PCIE-SOUTH") (pin "A14") (pinfunction "LVDS_3B_A14") (pintype "passive"))
    )
    (net (code "93") (name "B15_L24_N") (class "Default")
      (node (ref "JM2") (pin "37") (pinfunction "37_37") (pintype "bidirectional"))
    )
    (net (code "94") (name "B15_L24_P") (class "Default")
      (node (ref "JM2") (pin "39") (pinfunction "39_39") (pintype "bidirectional"))
    )
    (net (code "95") (name "B34_L1_N") (class "Default")
      (node (ref "JM1") (pin "37") (pinfunction "37_37") (pintype "bidirectional"))
    )
    (net (code "96") (name "B34_L1_P") (class "Default")
      (node (ref "JM1") (pin "35") (pinfunction "35_35") (pintype "bidirectional"))
    )
    (net (code "97") (name "B34_L2_N") (class "Default")
      (node (ref "JM1") (pin "33") (pinfunction "33_33") (pintype "bidirectional"))
    )
    (net (code "98") (name "B34_L2_P") (class "Default")
      (node (ref "JM1") (pin "31") (pinfunction "31_31") (pintype "bidirectional"))
    )
    (net (code "99") (name "B34_L3_N") (class "Default")
      (node (ref "JM1") (pin "42") (pinfunction "42_42") (pintype "bidirectional"))
      (node (ref "U4") (pin "13") (pinfunction "SCLK_13") (pintype "input"))
    )
    (net (code "100") (name "B34_L3_P") (class "Default")
      (node (ref "JM1") (pin "40") (pinfunction "40_40") (pintype "bidirectional"))
      (node (ref "U4") (pin "17") (pinfunction "GPIO0_17") (pintype "bidirectional"))
    )
    (net (code "101") (name "B34_L4_N") (class "Default")
      (node (ref "JM1") (pin "41") (pinfunction "41_41") (pintype "bidirectional"))
      (node (ref "U4") (pin "12") (pinfunction "SDOUT_12") (pintype "output"))
    )
    (net (code "102") (name "B34_L4_P") (class "Default")
      (node (ref "JM1") (pin "39") (pinfunction "39_39") (pintype "bidirectional"))
    )
    (net (code "103") (name "B34_L5_N") (class "Default")
      (node (ref "JM1") (pin "45") (pinfunction "45_45") (pintype "bidirectional"))
      (node (ref "U4") (pin "10") (pinfunction "~{CS}_10") (pintype "input"))
    )
    (net (code "104") (name "B34_L5_P") (class "Default")
      (node (ref "JM1") (pin "43") (pinfunction "43_43") (pintype "bidirectional"))
      (node (ref "U4") (pin "11") (pinfunction "SDIN_11") (pintype "input"))
    )
    (net (code "105") (name "B34_L6_N") (class "Default")
      (node (ref "JM1") (pin "34") (pinfunction "34_34") (pintype "bidirectional"))
    )
    (net (code "106") (name "B34_L6_P") (class "Default")
      (node (ref "JM1") (pin "32") (pinfunction "32_32") (pintype "bidirectional"))
    )
    (net (code "107") (name "B34_L7_N") (class "Default")
      (node (ref "JM1") (pin "38") (pinfunction "38_38") (pintype "bidirectional"))
      (node (ref "U4") (pin "18") (pinfunction "GPIO1_18") (pintype "bidirectional"))
    )
    (net (code "108") (name "B34_L7_P") (class "Default")
      (node (ref "JM1") (pin "36") (pinfunction "36_36") (pintype "bidirectional"))
    )
    (net (code "109") (name "B34_L8_N") (class "Default")
      (node (ref "JM1") (pin "52") (pinfunction "52_52") (pintype "bidirectional"))
      (node (ref "U3") (pin "13") (pinfunction "SCLK_13") (pintype "input"))
    )
    (net (code "110") (name "B34_L8_P") (class "Default")
      (node (ref "JM1") (pin "50") (pinfunction "50_50") (pintype "bidirectional"))
      (node (ref "U3") (pin "12") (pinfunction "SDOUT_12") (pintype "output"))
    )
    (net (code "111") (name "B34_L9_N") (class "Default")
      (node (ref "JM1") (pin "46") (pinfunction "46_46") (pintype "bidirectional"))
      (node (ref "U4") (pin "33") (pinfunction "GPIO2_33") (pintype "bidirectional"))
    )
    (net (code "112") (name "B34_L9_P") (class "Default")
      (node (ref "JM1") (pin "44") (pinfunction "44_44") (pintype "bidirectional"))
      (node (ref "U4") (pin "36") (pinfunction "GPIO3_36") (pintype "bidirectional"))
    )
    (net (code "113") (name "B34_L10_N") (class "Default")
      (node (ref "JM1") (pin "51") (pinfunction "51_51") (pintype "bidirectional"))
      (node (ref "U5") (pin "11") (pinfunction "SDIN_11") (pintype "input"))
    )
    (net (code "114") (name "B34_L10_P") (class "Default")
      (node (ref "JM1") (pin "49") (pinfunction "49_49") (pintype "bidirectional"))
      (node (ref "U5") (pin "10") (pinfunction "~{CS}_10") (pintype "input"))
    )
    (net (code "115") (name "B34_L11_N") (class "Default")
      (node (ref "JM1") (pin "53") (pinfunction "53_53") (pintype "bidirectional"))
      (node (ref "U5") (pin "12") (pinfunction "SDOUT_12") (pintype "output"))
    )
    (net (code "116") (name "B34_L11_P") (class "Default")
      (node (ref "JM1") (pin "55") (pinfunction "55_55") (pintype "bidirectional"))
      (node (ref "U5") (pin "17") (pinfunction "GPIO0_17") (pintype "bidirectional"))
    )
    (net (code "117") (name "B34_L12_N") (class "Default")
      (node (ref "JM1") (pin "57") (pinfunction "57_57") (pintype "bidirectional"))
      (node (ref "U5") (pin "18") (pinfunction "GPIO1_18") (pintype "bidirectional"))
    )
    (net (code "118") (name "B34_L12_P") (class "Default")
      (node (ref "JM1") (pin "59") (pinfunction "59_59") (pintype "bidirectional"))
      (node (ref "U5") (pin "13") (pinfunction "SCLK_13") (pintype "input"))
    )
    (net (code "119") (name "B34_L13_N") (class "Default")
      (node (ref "JM1") (pin "56") (pinfunction "56_56") (pintype "bidirectional"))
      (node (ref "U3") (pin "18") (pinfunction "GPIO1_18") (pintype "bidirectional"))
    )
    (net (code "120") (name "B34_L13_P") (class "Default")
      (node (ref "JM1") (pin "54") (pinfunction "54_54") (pintype "bidirectional"))
      (node (ref "U3") (pin "17") (pinfunction "GPIO0_17") (pintype "bidirectional"))
    )
    (net (code "121") (name "B34_L14_N") (class "Default")
      (node (ref "JM1") (pin "60") (pinfunction "60_60") (pintype "bidirectional"))
      (node (ref "U3") (pin "36") (pinfunction "GPIO3_36") (pintype "bidirectional"))
    )
    (net (code "122") (name "B34_L14_P") (class "Default")
      (node (ref "JM1") (pin "58") (pinfunction "58_58") (pintype "bidirectional"))
      (node (ref "U3") (pin "33") (pinfunction "GPIO2_33") (pintype "bidirectional"))
    )
    (net (code "123") (name "B34_L15_N") (class "Default")
      (node (ref "JM1") (pin "62") (pinfunction "62_62") (pintype "bidirectional"))
    )
    (net (code "124") (name "B34_L15_P") (class "Default")
      (node (ref "JM1") (pin "64") (pinfunction "64_64") (pintype "bidirectional"))
    )
    (net (code "125") (name "B34_L16_N") (class "Default")
      (node (ref "JM1") (pin "68") (pinfunction "68_68") (pintype "bidirectional"))
    )
    (net (code "126") (name "B34_L16_P") (class "Default")
      (node (ref "JM1") (pin "70") (pinfunction "70_70") (pintype "bidirectional"))
      (node (ref "U4") (pin "32") (pinfunction "RCLK_32") (pintype "input"))
    )
    (net (code "127") (name "B34_L17_N") (class "Default")
      (node (ref "JM1") (pin "63") (pinfunction "63_63") (pintype "bidirectional"))
      (node (ref "U3") (pin "11") (pinfunction "SDIN_11") (pintype "input"))
    )
    (net (code "128") (name "B34_L17_P") (class "Default")
      (node (ref "JM1") (pin "65") (pinfunction "65_65") (pintype "bidirectional"))
      (node (ref "U3") (pin "10") (pinfunction "~{CS}_10") (pintype "input"))
    )
    (net (code "129") (name "B34_L18_N") (class "Default")
      (node (ref "JM1") (pin "74") (pinfunction "74_74") (pintype "bidirectional"))
    )
    (net (code "130") (name "B34_L18_P") (class "Default")
      (node (ref "JM1") (pin "72") (pinfunction "72_72") (pintype "bidirectional"))
    )
    (net (code "131") (name "B34_L19_N") (class "Default")
      (node (ref "JM1") (pin "71") (pinfunction "71_71") (pintype "bidirectional"))
    )
    (net (code "132") (name "B34_L19_P") (class "Default")
      (node (ref "JM1") (pin "73") (pinfunction "73_73") (pintype "bidirectional"))
      (node (ref "U5") (pin "32") (pinfunction "RCLK_32") (pintype "input"))
    )
    (net (code "133") (name "B34_L20_N") (class "Default")
      (node (ref "JM1") (pin "76") (pinfunction "76_76") (pintype "bidirectional"))
      (node (ref "R6") (pin "1") (pinfunction "1_1") (pintype "passive"))
    )
    (net (code "134") (name "B34_L20_P") (class "Default")
      (node (ref "JM1") (pin "78") (pinfunction "78_78") (pintype "bidirectional"))
      (node (ref "R7") (pin "1") (pinfunction "1_1") (pintype "passive"))
    )
    (net (code "135") (name "B34_L21_N") (class "Default")
      (node (ref "JM1") (pin "69") (pinfunction "69_69") (pintype "bidirectional"))
      (node (ref "U5") (pin "33") (pinfunction "GPIO2_33") (pintype "bidirectional"))
    )
    (net (code "136") (name "B34_L21_P") (class "Default")
      (node (ref "JM1") (pin "67") (pinfunction "67_67") (pintype "bidirectional"))
      (node (ref "U5") (pin "36") (pinfunction "GPIO3_36") (pintype "bidirectional"))
    )
    (net (code "137") (name "B34_L22_N") (class "Default")
      (node (ref "JM1") (pin "75") (pinfunction "75_75") (pintype "bidirectional"))
    )
    (net (code "138") (name "B34_L22_P") (class "Default")
      (node (ref "JM1") (pin "77") (pinfunction "77_77") (pintype "bidirectional"))
    )
    (net (code "139") (name "B34_L23_N") (class "Default")
      (node (ref "JM1") (pin "79") (pinfunction "79_79") (pintype "bidirectional"))
    )
    (net (code "140") (name "B34_L23_P") (class "Default")
      (node (ref "JM1") (pin "81") (pinfunction "81_81") (pintype "bidirectional"))
    )
    (net (code "141") (name "B34_L24_N") (class "Default")
      (node (ref "JM1") (pin "80") (pinfunction "80_80") (pintype "bidirectional"))
      (node (ref "R8") (pin "1") (pinfunction "1_1") (pintype "passive"))
    )
    (net (code "142") (name "B34_L24_P") (class "Default")
      (node (ref "JM1") (pin "82") (pinfunction "82_82") (pintype "bidirectional"))
      (node (ref "R9") (pin "1") (pinfunction "1_1") (pintype "passive"))
    )
    (net (code "143") (name "BOOTMODE") (class "Default")
      (node (ref "JM2") (pin "100") (pinfunction "100_100") (pintype "bidirectional"))
    )
    (net (code "144") (name "DONE") (class "Default")
      (node (ref "D5") (pin "A") (pinfunction "A_A") (pintype "passive"))
      (node (ref "JM1") (pin "96") (pinfunction "96_96") (pintype "bidirectional"))
      (node (ref "R4") (pin "1") (pinfunction "1_1") (pintype "passive"))
    )
    (net (code "145") (name "EN_A") (class "Default")
      (node (ref "R18") (pin "1") (pinfunction "1_1") (pintype "passive"))
      (node (ref "U6") (pin "1") (pinfunction "EN_1") (pintype "input"))
    )
    (net (code "146") (name "EN_B") (class "Default")
      (node (ref "R21") (pin "1") (pinfunction "1_1") (pintype "passive"))
      (node (ref "U7") (pin "1") (pinfunction "EN_1") (pintype "input"))
    )
    (net (code "147") (name "GND") (class "Default")
      (node (ref "C1") (pin "2") (pinfunction "2_2") (pintype "passive"))
      (node (ref "C10") (pin "2") (pinfunction "2_2") (pintype "passive"))
      (node (ref "C11") (pin "2") (pinfunction "2_2") (pintype "passive"))
      (node (ref "C12") (pin "2") (pinfunction "2_2") (pintype "passive"))
      (node (ref "C13") (pin "2") (pinfunction "2_2") (pintype "passive"))
      (node (ref "C14") (pin "2") (pinfunction "2_2") (pintype "passive"))
      (node (ref "C15") (pin "2") (pinfunction "2_2") (pintype "passive"))
      (node (ref "C16") (pin "2") (pinfunction "2_2") (pintype "passive"))
      (node (ref "C17") (pin "2") (pinfunction "2_2") (pintype "passive"))
      (node (ref "C18") (pin "2") (pinfunction "2_2") (pintype "passive"))
      (node (ref "C19") (pin "2") (pinfunction "2_2") (pintype "passive"))
      (node (ref "C25") (pin "2") (pinfunction "2_2") (pintype "passive"))
      (node (ref "C26") (pin "2") (pinfunction "2_2") (pintype "passive"))
      (node (ref "C27") (pin "2") (pinfunction "2_2") (pintype "passive"))
      (node (ref "C28") (pin "2") (pinfunction "2_2") (pintype "passive"))
      (node (ref "C29") (pin "2") (pinfunction "2_2") (pintype "passive"))
      (node (ref "C30") (pin "2") (pinfunction "2_2") (pintype "passive"))
      (node (ref "C31") (pin "2") (pinfunction "2_2") (pintype "passive"))
      (node (ref "C32") (pin "2") (pinfunction "2_2") (pintype "passive"))
      (node (ref "C33") (pin "2") (pinfunction "2_2") (pintype "passive"))
      (node (ref "C34") (pin "2") (pinfunction "2_2") (pintype "passive"))
      (node (ref "C35") (pin "2") (pinfunction "2_2") (pintype "passive"))
      (node (ref "C36") (pin "2") (pinfunction "2_2") (pintype "passive"))
      (node (ref "C37") (pin "2") (pinfunction "2_2") (pintype "passive"))
      (node (ref "C4") (pin "2") (pinfunction "2_2") (pintype "passive"))
      (node (ref "C43") (pin "2") (pinfunction "2_2") (pintype "passive"))
      (node (ref "C44") (pin "2") (pinfunction "2_2") (pintype "passive"))
      (node (ref "C45") (pin "2") (pinfunction "2_2") (pintype "passive"))
      (node (ref "C46") (pin "2") (pinfunction "2_2") (pintype "passive"))
      (node (ref "C47") (pin "2") (pinfunction "2_2") (pintype "passive"))
      (node (ref "C48") (pin "2") (pinfunction "2_2") (pintype "passive"))
      (node (ref "C49") (pin "2") (pinfunction "2_2") (pintype "passive"))
      (node (ref "C50") (pin "2") (pinfunction "2_2") (pintype "passive"))
      (node (ref "C51") (pin "2") (pinfunction "2_2") (pintype "passive"))
      (node (ref "C52") (pin "2") (pinfunction "2_2") (pintype "passive"))
      (node (ref "C53") (pin "2") (pinfunction "2_2") (pintype "passive"))
      (node (ref "C54") (pin "2") (pinfunction "2_2") (pintype "passive"))
      (node (ref "C55") (pin "2") (pinfunction "2_2") (pintype "passive"))
      (node (ref "C56") (pin "2") (pinfunction "2_2") (pintype "passive"))
      (node (ref "C57") (pin "2") (pinfunction "2_2") (pintype "passive"))
      (node (ref "C58") (pin "2") (pinfunction "2_2") (pintype "passive"))
      (node (ref "C59") (pin "2") (pinfunction "2_2") (pintype "passive"))
      (node (ref "C8") (pin "2") (pinfunction "2_2") (pintype "passive"))
      (node (ref "C9") (pin "2") (pinfunction "2_2") (pintype "passive"))
      (node (ref "D5") (pin "C") (pinfunction "C_C") (pintype "passive"))
      (node (ref "JM1") (pin "100") (pinfunction "100_100") (pintype "bidirectional"))
      (node (ref "JM1") (pin "11") (pinfunction "11_11") (pintype "bidirectional"))
      (node (ref "JM1") (pin "12") (pinfunction "12_12") (pintype "bidirectional"))
      (node (ref "JM1") (pin "17") (pinfunction "17_17") (pintype "bidirectional"))
      (node (ref "JM1") (pin "18") (pinfunction "18_18") (pintype "bidirectional"))
      (node (ref "JM1") (pin "23") (pinfunction "23_23") (pintype "bidirectional"))
      (node (ref "JM1") (pin "24") (pinfunction "24_24") (pintype "bidirectional"))
      (node (ref "JM1") (pin "29") (pinfunction "29_29") (pintype "bidirectional"))
      (node (ref "JM1") (pin "30") (pinfunction "30_30") (pintype "bidirectional"))
      (node (ref "JM1") (pin "47") (pinfunction "47_47") (pintype "bidirectional"))
      (node (ref "JM1") (pin "48") (pinfunction "48_48") (pintype "bidirectional"))
      (node (ref "JM1") (pin "5") (pinfunction "5_5") (pintype "bidirectional"))
      (node (ref "JM1") (pin "6") (pinfunction "6_6") (pintype "bidirectional"))
      (node (ref "JM1") (pin "66") (pinfunction "66_66") (pintype "bidirectional"))
      (node (ref "JM1") (pin "84") (pinfunction "84_84") (pintype "bidirectional"))
      (node (ref "JM1") (pin "98") (pinfunction "98_98") (pintype "bidirectional"))
      (node (ref "JM1") (pin "F1") (pinfunction "F1_F1") (pintype "bidirectional"))
      (node (ref "JM1") (pin "F2") (pinfunction "F2_F2") (pintype "bidirectional"))
      (node (ref "JM2") (pin "17") (pinfunction "17_17") (pintype "bidirectional"))
      (node (ref "JM2") (pin "35") (pinfunction "35_35") (pintype "bidirectional"))
      (node (ref "JM2") (pin "36") (pinfunction "36_36") (pintype "bidirectional"))
      (node (ref "JM2") (pin "72") (pinfunction "72_72") (pintype "bidirectional"))
      (node (ref "JM2") (pin "83") (pinfunction "83_83") (pintype "bidirectional"))
      (node (ref "JM2") (pin "90") (pinfunction "90_90") (pintype "bidirectional"))
      (node (ref "JM2") (pin "F1") (pinfunction "F1_F1") (pintype "bidirectional"))
      (node (ref "JM2") (pin "F2") (pinfunction "F2_F2") (pintype "bidirectional"))
      (node (ref "JP1") (pin "3") (pinfunction "3_3") (pintype "passive"))
      (node (ref "JTAG") (pin "1") (pinfunction "1_1") (pintype "passive"))
      (node (ref "JTAG") (pin "11") (pinfunction "11_11") (pintype "passive"))
      (node (ref "JTAG") (pin "13") (pinfunction "13_13") (pintype "passive"))
      (node (ref "JTAG") (pin "3") (pinfunction "3_3") (pintype "passive"))
      (node (ref "JTAG") (pin "5") (pinfunction "5_5") (pintype "passive"))
      (node (ref "JTAG") (pin "7") (pinfunction "7_7") (pintype "passive"))
      (node (ref "JTAG") (pin "9") (pinfunction "9_9") (pintype "passive"))
      (node (ref "OUT1") (pin "2@1") (pinfunction "GND_2@1") (pintype "passive"))
      (node (ref "OUT1") (pin "2@2") (pinfunction "GND_2@2") (pintype "passive"))
      (node (ref "OUT1") (pin "2@3") (pinfunction "GND_2@3") (pintype "passive"))
      (node (ref "OUT2") (pin "2@1") (pinfunction "GND_2@1") (pintype "passive"))
      (node (ref "OUT2") (pin "2@2") (pinfunction "GND_2@2") (pintype "passive"))
      (node (ref "OUT2") (pin "2@3") (pinfunction "GND_2@3") (pintype "passive"))
      (node (ref "PCIE-NORTH") (pin "A1") (pinfunction "GND_A1") (pintype "passive"))
      (node (ref "PCIE-NORTH") (pin "A10") (pinfunction "GND_A10") (pintype "passive"))
      (node (ref "PCIE-NORTH") (pin "A12") (pinfunction "GND_A12") (pintype "passive"))
      (node (ref "PCIE-NORTH") (pin "A15") (pinfunction "GND_A15") (pintype "passive"))
      (node (ref "PCIE-NORTH") (pin "A18") (pinfunction "GND_A18") (pintype "passive"))
      (node (ref "PCIE-NORTH") (pin "A4") (pinfunction "GND_A4") (pintype "passive"))
      (node (ref "PCIE-NORTH") (pin "A7") (pinfunction "GND_A7") (pintype "passive"))
      (node (ref "PCIE-NORTH") (pin "B15") (pinfunction "GND_B15") (pintype "passive"))
      (node (ref "PCIE-NORTH") (pin "B18") (pinfunction "GND_B18") (pintype "passive"))
      (node (ref "PCIE-SOUTH") (pin "A1") (pinfunction "GND_A1") (pintype "passive"))
      (node (ref "PCIE-SOUTH") (pin "A10") (pinfunction "GND_A10") (pintype "passive"))
      (node (ref "PCIE-SOUTH") (pin "A12") (pinfunction "GND_A12") (pintype "passive"))
      (node (ref "PCIE-SOUTH") (pin "A15") (pinfunction "GND_A15") (pintype "passive"))
      (node (ref "PCIE-SOUTH") (pin "A18") (pinfunction "GND_A18") (pintype "passive"))
      (node (ref "PCIE-SOUTH") (pin "A4") (pinfunction "GND_A4") (pintype "passive"))
      (node (ref "PCIE-SOUTH") (pin "A7") (pinfunction "GND_A7") (pintype "passive"))
      (node (ref "PCIE-SOUTH") (pin "B15") (pinfunction "GND_B15") (pintype "passive"))
      (node (ref "PCIE-SOUTH") (pin "B18") (pinfunction "GND_B18") (pintype "passive"))
      (node (ref "R10") (pin "2") (pinfunction "2_2") (pintype "passive"))
      (node (ref "R11") (pin "2") (pinfunction "2_2") (pintype "passive"))
      (node (ref "R12") (pin "2") (pinfunction "2_2") (pintype "passive"))
      (node (ref "R13") (pin "2") (pinfunction "2_2") (pintype "passive"))
      (node (ref "R14") (pin "2") (pinfunction "2_2") (pintype "passive"))
      (node (ref "R15") (pin "2") (pinfunction "2_2") (pintype "passive"))
      (node (ref "R16") (pin "2") (pinfunction "2_2") (pintype "passive"))
      (node (ref "R19") (pin "1") (pinfunction "1_1") (pintype "passive"))
      (node (ref "R22") (pin "1") (pinfunction "1_1") (pintype "passive"))
      (node (ref "R3") (pin "2") (pinfunction "2_2") (pintype "passive"))
      (node (ref "SDI-IN") (pin "2@1") (pinfunction "GND_2@1") (pintype "passive"))
      (node (ref "SDI-IN") (pin "2@2") (pinfunction "GND_2@2") (pintype "passive"))
      (node (ref "SDI-IN") (pin "2@3") (pinfunction "GND_2@3") (pintype "passive"))
      (node (ref "U1") (pin "3") (pinfunction "GND_3") (pintype "passive"))
      (node (ref "U2") (pin "1") (pinfunction "A0_1") (pintype "input"))
      (node (ref "U2") (pin "2") (pinfunction "A1_2") (pintype "input"))
      (node (ref "U2") (pin "3") (pinfunction "A2_3") (pintype "input"))
      (node (ref "U2") (pin "4") (pinfunction "GND_4") (pintype "passive"))
      (node (ref "U2") (pin "EP") (pinfunction "EP_EP") (pintype "passive"))
      (node (ref "U3") (pin "1") (pinfunction "VEE_SDI_1") (pintype "power_in"))
      (node (ref "U3") (pin "14") (pinfunction "VSS_14") (pintype "power_in"))
      (node (ref "U3") (pin "15") (pinfunction "VSS_15") (pintype "power_in"))
      (node (ref "U3") (pin "19") (pinfunction "VEE_CORE_19") (pintype "power_in"))
      (node (ref "U3") (pin "21") (pinfunction "VEEO_21") (pintype "power_in"))
      (node (ref "U3") (pin "28") (pinfunction "VEEO_28") (pintype "power_in"))
      (node (ref "U3") (pin "31") (pinfunction "VEE_CORE_31") (pintype "power_in"))
      (node (ref "U3") (pin "37") (pinfunction "VEE_CORE_37") (pintype "power_in"))
      (node (ref "U3") (pin "38") (pinfunction "VEE_CORE_38") (pintype "power_in"))
      (node (ref "U3") (pin "8") (pinfunction "VEE_SDI_8") (pintype "power_in"))
      (node (ref "U4") (pin "1") (pinfunction "VEE_DDI_1") (pintype "power_in"))
      (node (ref "U4") (pin "14") (pinfunction "VSS_14") (pintype "power_in"))
      (node (ref "U4") (pin "15") (pinfunction "VSS_15") (pintype "power_in"))
      (node (ref "U4") (pin "19") (pinfunction "VEE_CORE_19") (pintype "power_in"))
      (node (ref "U4") (pin "21") (pinfunction "VEEO_21") (pintype "power_in"))
      (node (ref "U4") (pin "28") (pinfunction "VEEO_28") (pintype "power_in"))
      (node (ref "U4") (pin "31") (pinfunction "VEE_CORE_31") (pintype "power_in"))
      (node (ref "U4") (pin "37") (pinfunction "VEE_CORE_37") (pintype "power_in"))
      (node (ref "U4") (pin "38") (pinfunction "VEE_CORE_38") (pintype "power_in"))
      (node (ref "U4") (pin "8") (pinfunction "VEE_DDI_8") (pintype "power_in"))
      (node (ref "U5") (pin "1") (pinfunction "VEE_DDI_1") (pintype "power_in"))
      (node (ref "U5") (pin "14") (pinfunction "VSS_14") (pintype "power_in"))
      (node (ref "U5") (pin "15") (pinfunction "VSS_15") (pintype "power_in"))
      (node (ref "U5") (pin "19") (pinfunction "VEE_CORE_19") (pintype "power_in"))
      (node (ref "U5") (pin "21") (pinfunction "VEEO_21") (pintype "power_in"))
      (node (ref "U5") (pin "28") (pinfunction "VEEO_28") (pintype "power_in"))
      (node (ref "U5") (pin "31") (pinfunction "VEE_CORE_31") (pintype "power_in"))
      (node (ref "U5") (pin "37") (pinfunction "VEE_CORE_37") (pintype "power_in"))
      (node (ref "U5") (pin "38") (pinfunction "VEE_CORE_38") (pintype "power_in"))
      (node (ref "U5") (pin "8") (pinfunction "VEE_DDI_8") (pintype "power_in"))
      (node (ref "U6") (pin "5") (pinfunction "GND_5") (pintype "passive"))
      (node (ref "U6") (pin "6") (pinfunction "GND_6") (pintype "passive"))
      (node (ref "U6") (pin "EP") (pinfunction "GND_EP") (pintype "passive"))
      (node (ref "U7") (pin "5") (pinfunction "GND_5") (pintype "passive"))
      (node (ref "U7") (pin "6") (pinfunction "GND_6") (pintype "passive"))
      (node (ref "U7") (pin "EP") (pinfunction "GND_EP") (pintype "passive"))
    )
    (net (code "148") (name "I2C_V") (class "Default")
      (node (ref "C4") (pin "1") (pinfunction "1_1") (pintype "passive"))
      (node (ref "PCIE-NORTH") (pin "B3") (pinfunction "V_I2C_B3") (pintype "passive"))
      (node (ref "R2") (pin "1") (pinfunction "1_1") (pintype "passive"))
      (node (ref "U2") (pin "8") (pinfunction "VCC_8") (pintype "power_in"))
    )
    (net (code "149") (name "MGT_CLK0_N") (class "Default")
      (node (ref "C3") (pin "2") (pinfunction "2_2") (pintype "passive"))
      (node (ref "JM1") (pin "4") (pinfunction "4_4") (pintype "bidirectional"))
    )
    (net (code "150") (name "MGT_CLK0_P") (class "Default")
      (node (ref "C2") (pin "2") (pinfunction "2_2") (pintype "passive"))
      (node (ref "JM1") (pin "2") (pinfunction "2_2") (pintype "bidirectional"))
    )
    (net (code "151") (name "MGT_RX0_N") (class "Default")
      (node (ref "JM1") (pin "21") (pinfunction "21_21") (pintype "bidirectional"))
      (node (ref "U3") (pin "27") (pinfunction "DDO0_27") (pintype "output"))
    )
    (net (code "152") (name "MGT_RX0_P") (class "Default")
      (node (ref "JM1") (pin "19") (pinfunction "19_19") (pintype "bidirectional"))
      (node (ref "U3") (pin "26") (pinfunction "~{DDO0}_26") (pintype "output"))
    )
    (net (code "153") (name "MGT_RX1_N") (class "Default")
      (node (ref "JM1") (pin "15") (pinfunction "15_15") (pintype "bidirectional"))
      (node (ref "U3") (pin "23") (pinfunction "DDO1/RCO_23") (pintype "output"))
    )
    (net (code "154") (name "MGT_RX1_P") (class "Default")
      (node (ref "JM1") (pin "13") (pinfunction "13_13") (pintype "bidirectional"))
      (node (ref "U3") (pin "22") (pinfunction "~{DDO1}/~{RCO}_22") (pintype "output"))
    )
    (net (code "155") (name "MGT_RX2_N") (class "Default")
      (node (ref "JM1") (pin "9") (pinfunction "9_9") (pintype "bidirectional"))
    )
    (net (code "156") (name "MGT_RX2_P") (class "Default")
      (node (ref "JM1") (pin "7") (pinfunction "7_7") (pintype "bidirectional"))
    )
    (net (code "157") (name "MGT_RX3_N") (class "Default")
      (node (ref "JM1") (pin "3") (pinfunction "3_3") (pintype "bidirectional"))
    )
    (net (code "158") (name "MGT_RX3_P") (class "Default")
      (node (ref "JM1") (pin "1") (pinfunction "1_1") (pintype "bidirectional"))
    )
    (net (code "159") (name "MGT_TX0_N") (class "Default")
      (node (ref "JM1") (pin "28") (pinfunction "28_28") (pintype "bidirectional"))
      (node (ref "U5") (pin "6") (pinfunction "DDI_6") (pintype "input"))
    )
    (net (code "160") (name "MGT_TX0_P") (class "Default")
      (node (ref "JM1") (pin "26") (pinfunction "26_26") (pintype "bidirectional"))
      (node (ref "U5") (pin "7") (pinfunction "~{DDI}_7") (pintype "input"))
    )
    (net (code "161") (name "MGT_TX1_N") (class "Default")
      (node (ref "JM1") (pin "22") (pinfunction "22_22") (pintype "bidirectional"))
      (node (ref "U4") (pin "6") (pinfunction "DDI_6") (pintype "input"))
    )
    (net (code "162") (name "MGT_TX1_P") (class "Default")
      (node (ref "JM1") (pin "20") (pinfunction "20_20") (pintype "bidirectional"))
      (node (ref "U4") (pin "7") (pinfunction "~{DDI}_7") (pintype "input"))
    )
    (net (code "163") (name "MGT_TX2_N") (class "Default")
      (node (ref "JM1") (pin "16") (pinfunction "16_16") (pintype "bidirectional"))
    )
    (net (code "164") (name "MGT_TX2_P") (class "Default")
      (node (ref "JM1") (pin "14") (pinfunction "14_14") (pintype "bidirectional"))
    )
    (net (code "165") (name "MGT_TX3_N") (class "Default")
      (node (ref "JM1") (pin "10") (pinfunction "10_10") (pintype "bidirectional"))
    )
    (net (code "166") (name "MGT_TX3_P") (class "Default")
      (node (ref "JM1") (pin "8") (pinfunction "8_8") (pintype "bidirectional"))
    )
    (net (code "167") (name "M_1V8") (class "Default")
      (node (ref "JM2") (pin "18") (pinfunction "18_18") (pintype "bidirectional"))
      (node (ref "R5") (pin "2") (pinfunction "2_2") (pintype "passive"))
    )
    (net (code "168") (name "N_5V") (class "Default")
      (node (ref "PCIE-NORTH") (pin "B12") (pinfunction "5V_B12") (pintype "passive"))
    )
    (net (code "169") (name "N_IO0") (class "Default")
      (node (ref "PCIE-NORTH") (pin "B4") (pinfunction "IO0_B4") (pintype "passive"))
    )
    (net (code "170") (name "N_IO1") (class "Default")
      (node (ref "PCIE-NORTH") (pin "B5") (pinfunction "IO1_B5") (pintype "passive"))
    )
    (net (code "171") (name "N_IO2") (class "Default")
      (node (ref "PCIE-NORTH") (pin "B6") (pinfunction "IO2_B6") (pintype "passive"))
    )
    (net (code "172") (name "N_IO3") (class "Default")
      (node (ref "PCIE-NORTH") (pin "B7") (pinfunction "IO3_B7") (pintype "passive"))
    )
    (net (code "173") (name "N_IO4") (class "Default")
      (node (ref "PCIE-NORTH") (pin "B8") (pinfunction "IO4_B8") (pintype "passive"))
    )
    (net (code "174") (name "N_IO5") (class "Default")
      (node (ref "PCIE-NORTH") (pin "B9") (pinfunction "IO5_B9") (pintype "passive"))
    )
    (net (code "175") (name "N_IO6") (class "Default")
      (node (ref "PCIE-NORTH") (pin "B10") (pinfunction "IO6_B10") (pintype "passive"))
    )
    (net (code "176") (name "N_IO7") (class "Default")
      (node (ref "PCIE-NORTH") (pin "B11") (pinfunction "IO7_B11") (pintype "passive"))
    )
    (net (code "177") (name "N_PCIE_V") (class "Default")
      (node (ref "PCIE-NORTH") (pin "B13") (pinfunction "VCC_B13") (pintype "passive"))
    )
    (net (code "178") (name "N_VCCIO") (class "Default")
      (node (ref "PCIE-NORTH") (pin "B14") (pinfunction "VCCIO_B14") (pintype "passive"))
    )
    (net (code "179") (name "Net-(C5-Pad1)") (class "Default")
      (node (ref "C5") (pin "1") (pinfunction "1_1") (pintype "passive"))
      (node (ref "SDI-IN") (pin "1") (pinfunction "1_1") (pintype "passive"))
    )
    (net (code "180") (name "Net-(C7-Pad2)") (class "Default")
      (node (ref "C7") (pin "2") (pinfunction "2_2") (pintype "passive"))
      (node (ref "R10") (pin "1") (pinfunction "1_1") (pintype "passive"))
    )
    (net (code "181") (name "Net-(C20-Pad2)") (class "Default")
      (node (ref "C20") (pin "2") (pinfunction "2_2") (pintype "passive"))
      (node (ref "OUT1") (pin "1") (pinfunction "1_1") (pintype "passive"))
    )
    (net (code "182") (name "Net-(C21-Pad2)") (class "Default")
      (node (ref "C21") (pin "2") (pinfunction "2_2") (pintype "passive"))
      (node (ref "R11") (pin "1") (pinfunction "1_1") (pintype "passive"))
    )
    (net (code "183") (name "Net-(C22-Pad2)") (class "Default")
      (node (ref "C22") (pin "2") (pinfunction "2_2") (pintype "passive"))
      (node (ref "R12") (pin "1") (pinfunction "1_1") (pintype "passive"))
    )
    (net (code "184") (name "Net-(C23-Pad2)") (class "Default")
      (node (ref "C23") (pin "2") (pinfunction "2_2") (pintype "passive"))
      (node (ref "R13") (pin "1") (pinfunction "1_1") (pintype "passive"))
    )
    (net (code "185") (name "Net-(C38-Pad2)") (class "Default")
      (node (ref "C38") (pin "2") (pinfunction "2_2") (pintype "passive"))
      (node (ref "OUT2") (pin "1") (pinfunction "1_1") (pintype "passive"))
    )
    (net (code "186") (name "Net-(C39-Pad2)") (class "Default")
      (node (ref "C39") (pin "2") (pinfunction "2_2") (pintype "passive"))
      (node (ref "R14") (pin "1") (pinfunction "1_1") (pintype "passive"))
    )
    (net (code "187") (name "Net-(C40-Pad2)") (class "Default")
      (node (ref "C40") (pin "2") (pinfunction "2_2") (pintype "passive"))
      (node (ref "R15") (pin "1") (pinfunction "1_1") (pintype "passive"))
    )
    (net (code "188") (name "Net-(C41-Pad2)") (class "Default")
      (node (ref "C41") (pin "2") (pinfunction "2_2") (pintype "passive"))
      (node (ref "R16") (pin "1") (pinfunction "1_1") (pintype "passive"))
    )
    (net (code "189") (name "Net-(D1-PadC)") (class "Default")
      (node (ref "D1") (pin "C") (pinfunction "C_C") (pintype "passive"))
      (node (ref "R6") (pin "2") (pinfunction "2_2") (pintype "passive"))
    )
    (net (code "190") (name "Net-(D2-PadC)") (class "Default")
      (node (ref "D2") (pin "C") (pinfunction "C_C") (pintype "passive"))
      (node (ref "R7") (pin "2") (pinfunction "2_2") (pintype "passive"))
    )
    (net (code "191") (name "Net-(D3-PadC)") (class "Default")
      (node (ref "D3") (pin "C") (pinfunction "C_C") (pintype "passive"))
      (node (ref "R8") (pin "2") (pinfunction "2_2") (pintype "passive"))
    )
    (net (code "192") (name "Net-(D4-PadC)") (class "Default")
      (node (ref "D4") (pin "C") (pinfunction "C_C") (pintype "passive"))
      (node (ref "R9") (pin "2") (pinfunction "2_2") (pintype "passive"))
    )
    (net (code "193") (name "Net-(U1-OUT+)") (class "Default")
      (node (ref "C2") (pin "1") (pinfunction "1_1") (pintype "passive"))
      (node (ref "R1") (pin "1") (pinfunction "1_1") (pintype "passive"))
      (node (ref "U1") (pin "4") (pinfunction "OUT+_4") (pintype "output"))
    )
    (net (code "194") (name "Net-(U1-OUT-)") (class "Default")
      (node (ref "C3") (pin "1") (pinfunction "1_1") (pintype "passive"))
      (node (ref "R1") (pin "2") (pinfunction "2_2") (pintype "passive"))
      (node (ref "U1") (pin "5") (pinfunction "OUT-_5") (pintype "output"))
    )
    (net (code "195") (name "Net-(U2-WP)") (class "Default")
      (node (ref "R2") (pin "2") (pinfunction "2_2") (pintype "passive"))
      (node (ref "R3") (pin "1") (pinfunction "1_1") (pintype "passive"))
      (node (ref "U2") (pin "7") (pinfunction "WP_7") (pintype "input"))
    )
    (net (code "196") (name "Net-(U3-LF+)") (class "Default")
      (node (ref "C6") (pin "1") (pinfunction "1_1") (pintype "passive"))
      (node (ref "U3") (pin "39") (pinfunction "LF+_39") (pintype "passive"))
    )
    (net (code "197") (name "Net-(U3-LF-)") (class "Default")
      (node (ref "C6") (pin "2") (pinfunction "2_2") (pintype "passive"))
      (node (ref "U3") (pin "40") (pinfunction "LF-_40") (pintype "passive"))
    )
    (net (code "198") (name "Net-(U3-SDI)") (class "Default")
      (node (ref "C5") (pin "2") (pinfunction "2_2") (pintype "passive"))
      (node (ref "U3") (pin "2") (pinfunction "SDI_2") (pintype "input"))
    )
    (net (code "199") (name "Net-(U3-SDI_TERM)") (class "Default")
      (node (ref "C7") (pin "1") (pinfunction "1_1") (pintype "passive"))
      (node (ref "U3") (pin "3") (pinfunction "SDI_TERM_3") (pintype "passive"))
    )
    (net (code "200") (name "Net-(U3-VCO_FILT)") (class "Default")
      (node (ref "C8") (pin "1") (pinfunction "1_1") (pintype "passive"))
      (node (ref "U3") (pin "34") (pinfunction "VCO_FILT_34") (pintype "passive"))
    )
    (net (code "201") (name "Net-(U3-VCO_FILT10)") (class "Default")
      (node (ref "C9") (pin "1") (pinfunction "1_1") (pintype "passive"))
      (node (ref "U3") (pin "30") (pinfunction "VCO_FILT10_30") (pintype "passive"))
    )
    (net (code "202") (name "Net-(U4-LF+)") (class "Default")
      (node (ref "C24") (pin "1") (pinfunction "1_1") (pintype "passive"))
      (node (ref "U4") (pin "39") (pinfunction "LF+_39") (pintype "passive"))
    )
    (net (code "203") (name "Net-(U4-LF-)") (class "Default")
      (node (ref "C24") (pin "2") (pinfunction "2_2") (pintype "passive"))
      (node (ref "U4") (pin "40") (pinfunction "LF-_40") (pintype "passive"))
    )
    (net (code "204") (name "Net-(U4-SDO0)") (class "Default")
      (node (ref "C20") (pin "1") (pinfunction "1_1") (pintype "passive"))
      (node (ref "U4") (pin "27") (pinfunction "SDO0_27") (pintype "output"))
    )
    (net (code "205") (name "Net-(U4-SDO1{slash}RCO)") (class "Default")
      (node (ref "C22") (pin "1") (pinfunction "1_1") (pintype "passive"))
      (node (ref "U4") (pin "23") (pinfunction "SDO1/RCO_23") (pintype "output"))
    )
    (net (code "206") (name "Net-(U4-TERM)") (class "Default")
      (node (ref "C25") (pin "1") (pinfunction "1_1") (pintype "passive"))
      (node (ref "U4") (pin "5") (pinfunction "TERM_5") (pintype "passive"))
    )
    (net (code "207") (name "Net-(U4-VCO_FILT)") (class "Default")
      (node (ref "C26") (pin "1") (pinfunction "1_1") (pintype "passive"))
      (node (ref "U4") (pin "34") (pinfunction "VCO_FILT_34") (pintype "passive"))
    )
    (net (code "208") (name "Net-(U4-VCO_FILT10)") (class "Default")
      (node (ref "C27") (pin "1") (pinfunction "1_1") (pintype "passive"))
      (node (ref "U4") (pin "30") (pinfunction "VCO_FILT10_30") (pintype "passive"))
    )
    (net (code "209") (name "Net-(U4-~{SDO0})") (class "Default")
      (node (ref "C23") (pin "1") (pinfunction "1_1") (pintype "passive"))
      (node (ref "U4") (pin "26") (pinfunction "~{SDO0}_26") (pintype "output"))
    )
    (net (code "210") (name "Net-(U4-~{SDO1}{slash}~{RCO})") (class "Default")
      (node (ref "C21") (pin "1") (pinfunction "1_1") (pintype "passive"))
      (node (ref "U4") (pin "22") (pinfunction "~{SDO1}/~{RCO}_22") (pintype "output"))
    )
    (net (code "211") (name "Net-(U5-LF+)") (class "Default")
      (node (ref "C42") (pin "1") (pinfunction "1_1") (pintype "passive"))
      (node (ref "U5") (pin "39") (pinfunction "LF+_39") (pintype "passive"))
    )
    (net (code "212") (name "Net-(U5-LF-)") (class "Default")
      (node (ref "C42") (pin "2") (pinfunction "2_2") (pintype "passive"))
      (node (ref "U5") (pin "40") (pinfunction "LF-_40") (pintype "passive"))
    )
    (net (code "213") (name "Net-(U5-SDO0)") (class "Default")
      (node (ref "C41") (pin "1") (pinfunction "1_1") (pintype "passive"))
      (node (ref "U5") (pin "27") (pinfunction "SDO0_27") (pintype "output"))
    )
    (net (code "214") (name "Net-(U5-SDO1{slash}RCO)") (class "Default")
      (node (ref "C38") (pin "1") (pinfunction "1_1") (pintype "passive"))
      (node (ref "U5") (pin "23") (pinfunction "SDO1/RCO_23") (pintype "output"))
    )
    (net (code "215") (name "Net-(U5-TERM)") (class "Default")
      (node (ref "C43") (pin "1") (pinfunction "1_1") (pintype "passive"))
      (node (ref "U5") (pin "5") (pinfunction "TERM_5") (pintype "passive"))
    )
    (net (code "216") (name "Net-(U5-VCO_FILT)") (class "Default")
      (node (ref "C44") (pin "1") (pinfunction "1_1") (pintype "passive"))
      (node (ref "U5") (pin "34") (pinfunction "VCO_FILT_34") (pintype "passive"))
    )
    (net (code "217") (name "Net-(U5-VCO_FILT10)") (class "Default")
      (node (ref "C45") (pin "1") (pinfunction "1_1") (pintype "passive"))
      (node (ref "U5") (pin "30") (pinfunction "VCO_FILT10_30") (pintype "passive"))
    )
    (net (code "218") (name "Net-(U5-~{SDO0})") (class "Default")
      (node (ref "C40") (pin "1") (pinfunction "1_1") (pintype "passive"))
      (node (ref "U5") (pin "26") (pinfunction "~{SDO0}_26") (pintype "output"))
    )
    (net (code "219") (name "Net-(U5-~{SDO1}{slash}~{RCO})") (class "Default")
      (node (ref "C39") (pin "1") (pinfunction "1_1") (pintype "passive"))
      (node (ref "U5") (pin "22") (pinfunction "~{SDO1}/~{RCO}_22") (pintype "output"))
    )
    (net (code "220") (name "Net-(U6-FB)") (class "Default")
      (node (ref "R17") (pin "1") (pinfunction "1_1") (pintype "passive"))
      (node (ref "R19") (pin "2") (pinfunction "2_2") (pintype "passive"))
      (node (ref "U6") (pin "7") (pinfunction "FB_7") (pintype "output"))
    )
    (net (code "221") (name "Net-(U7-FB)") (class "Default")
      (node (ref "R20") (pin "1") (pinfunction "1_1") (pintype "passive"))
      (node (ref "R22") (pin "2") (pinfunction "2_2") (pintype "passive"))
      (node (ref "U7") (pin "7") (pinfunction "FB_7") (pintype "output"))
    )
    (net (code "222") (name "PROG_B") (class "Default")
      (node (ref "JM1") (pin "94") (pinfunction "94_94") (pintype "bidirectional"))
    )
    (net (code "223") (name "SCL") (class "Default")
      (node (ref "PCIE-NORTH") (pin "B2") (pinfunction "SCL_B2") (pintype "passive"))
      (node (ref "U2") (pin "6") (pinfunction "SCL_6") (pintype "input"))
    )
    (net (code "224") (name "SDA") (class "Default")
      (node (ref "PCIE-NORTH") (pin "B1") (pinfunction "SDA_B1") (pintype "passive"))
      (node (ref "U2") (pin "5") (pinfunction "SDA_5") (pintype "bidirectional"))
    )
    (net (code "225") (name "SPI-CLK") (class "Default")
      (node (ref "JM2") (pin "67") (pinfunction "67_67") (pintype "bidirectional"))
    )
    (net (code "226") (name "SPI-CS") (class "Default")
      (node (ref "JM2") (pin "69") (pinfunction "69_69") (pintype "bidirectional"))
    )
    (net (code "227") (name "SPI-DQ0") (class "Default")
      (node (ref "JM2") (pin "68") (pinfunction "68_68") (pintype "bidirectional"))
    )
    (net (code "228") (name "SPI-DQ1") (class "Default")
      (node (ref "JM2") (pin "71") (pinfunction "71_71") (pintype "bidirectional"))
    )
    (net (code "229") (name "SPI-DQ2") (class "Default")
      (node (ref "JM2") (pin "73") (pinfunction "73_73") (pintype "bidirectional"))
    )
    (net (code "230") (name "SPI-DQ3") (class "Default")
      (node (ref "JM2") (pin "70") (pinfunction "70_70") (pintype "bidirectional"))
    )
    (net (code "231") (name "S_5V") (class "Default")
      (node (ref "JP1") (pin "1") (pinfunction "1_1") (pintype "passive"))
      (node (ref "PCIE-SOUTH") (pin "B12") (pinfunction "5V_B12") (pintype "passive"))
    )
    (net (code "232") (name "S_PCIE_V") (class "Default")
      (node (ref "PCIE-SOUTH") (pin "B13") (pinfunction "VCC_B13") (pintype "passive"))
    )
    (net (code "233") (name "S_VCCIO") (class "Default")
      (node (ref "JM2") (pin "54") (pinfunction "54_54") (pintype "bidirectional"))
      (node (ref "PCIE-SOUTH") (pin "B14") (pinfunction "VCCIO_B14") (pintype "passive"))
    )
    (net (code "234") (name "TCK") (class "Default")
      (node (ref "JM1") (pin "90") (pinfunction "90_90") (pintype "bidirectional"))
      (node (ref "JTAG") (pin "6") (pinfunction "6_6") (pintype "passive"))
    )
    (net (code "235") (name "TDI") (class "Default")
      (node (ref "JM1") (pin "86") (pinfunction "86_86") (pintype "bidirectional"))
      (node (ref "JTAG") (pin "10") (pinfunction "10_10") (pintype "passive"))
    )
    (net (code "236") (name "TDO") (class "Default")
      (node (ref "JM1") (pin "88") (pinfunction "88_88") (pintype "bidirectional"))
      (node (ref "JTAG") (pin "8") (pinfunction "8_8") (pintype "passive"))
    )
    (net (code "237") (name "TMS") (class "Default")
      (node (ref "JM1") (pin "92") (pinfunction "92_92") (pintype "bidirectional"))
      (node (ref "JTAG") (pin "4") (pinfunction "4_4") (pintype "passive"))
    )
    (net (code "238") (name "VCCIO0") (class "Default")
      (node (ref "JM2") (pin "53") (pinfunction "53_53") (pintype "bidirectional"))
      (node (ref "JTAG") (pin "2") (pinfunction "2_2") (pintype "passive"))
    )
    (net (code "239") (name "VCCIO14") (class "Default")
      (node (ref "JM1") (pin "83") (pinfunction "83_83") (pintype "bidirectional"))
    )
    (net (code "240") (name "VCCO_4") (class "Default")
      (node (ref "C17") (pin "1") (pinfunction "1_1") (pintype "passive"))
      (node (ref "C18") (pin "1") (pinfunction "1_1") (pintype "passive"))
      (node (ref "C19") (pin "1") (pinfunction "1_1") (pintype "passive"))
      (node (ref "FB4") (pin "2") (pinfunction "2_2") (pintype "passive"))
      (node (ref "U3") (pin "24") (pinfunction "VCCO_1_24") (pintype "power_in"))
      (node (ref "U3") (pin "25") (pinfunction "VCCO_0_25") (pintype "power_in"))
    )
    (net (code "241") (name "VCCO_8") (class "Default")
      (node (ref "C35") (pin "1") (pinfunction "1_1") (pintype "passive"))
      (node (ref "C36") (pin "1") (pinfunction "1_1") (pintype "passive"))
      (node (ref "C37") (pin "1") (pinfunction "1_1") (pintype "passive"))
      (node (ref "FB7") (pin "2") (pinfunction "2_2") (pintype "passive"))
      (node (ref "U4") (pin "24") (pinfunction "VCCO_1_24") (pintype "power_in"))
      (node (ref "U4") (pin "25") (pinfunction "VCCO_0_25") (pintype "power_in"))
    )
    (net (code "242") (name "VCCO_9") (class "Default")
      (node (ref "C53") (pin "1") (pinfunction "1_1") (pintype "passive"))
      (node (ref "C54") (pin "1") (pinfunction "1_1") (pintype "passive"))
      (node (ref "C55") (pin "1") (pinfunction "1_1") (pintype "passive"))
      (node (ref "FB10") (pin "2") (pinfunction "2_2") (pintype "passive"))
      (node (ref "U5") (pin "24") (pinfunction "VCCO_1_24") (pintype "power_in"))
      (node (ref "U5") (pin "25") (pinfunction "VCCO_0_25") (pintype "power_in"))
    )
    (net (code "243") (name "VCC_4") (class "Default")
      (node (ref "C14") (pin "1") (pinfunction "1_1") (pintype "passive"))
      (node (ref "C15") (pin "1") (pinfunction "1_1") (pintype "passive"))
      (node (ref "C16") (pin "1") (pinfunction "1_1") (pintype "passive"))
      (node (ref "FB3") (pin "2") (pinfunction "2_2") (pintype "passive"))
      (node (ref "U3") (pin "35") (pinfunction "VCC_CORE_35") (pintype "power_in"))
      (node (ref "U3") (pin "4") (pinfunction "VCC_SDI_4") (pintype "power_in"))
    )
    (net (code "244") (name "VCC_8") (class "Default")
      (node (ref "C32") (pin "1") (pinfunction "1_1") (pintype "passive"))
      (node (ref "C33") (pin "1") (pinfunction "1_1") (pintype "passive"))
      (node (ref "C34") (pin "1") (pinfunction "1_1") (pintype "passive"))
      (node (ref "FB6") (pin "2") (pinfunction "2_2") (pintype "passive"))
      (node (ref "U4") (pin "35") (pinfunction "VCC_CORE_35") (pintype "power_in"))
      (node (ref "U4") (pin "4") (pinfunction "VCC_DDI_4") (pintype "power_in"))
    )
    (net (code "245") (name "VCC_9") (class "Default")
      (node (ref "C50") (pin "1") (pinfunction "1_1") (pintype "passive"))
      (node (ref "C51") (pin "1") (pinfunction "1_1") (pintype "passive"))
      (node (ref "C52") (pin "1") (pinfunction "1_1") (pintype "passive"))
      (node (ref "FB9") (pin "2") (pinfunction "2_2") (pintype "passive"))
      (node (ref "U5") (pin "35") (pinfunction "VCC_CORE_35") (pintype "power_in"))
      (node (ref "U5") (pin "4") (pinfunction "VCC_DDI_4") (pintype "power_in"))
    )
    (net (code "246") (name "VDD_4") (class "Default")
      (node (ref "C10") (pin "1") (pinfunction "1_1") (pintype "passive"))
      (node (ref "C11") (pin "1") (pinfunction "1_1") (pintype "passive"))
      (node (ref "C12") (pin "1") (pinfunction "1_1") (pintype "passive"))
      (node (ref "C13") (pin "1") (pinfunction "1_1") (pintype "passive"))
      (node (ref "FB2") (pin "2") (pinfunction "2_2") (pintype "passive"))
      (node (ref "U3") (pin "16") (pinfunction "VDD_16") (pintype "power_in"))
      (node (ref "U3") (pin "20") (pinfunction "VCCO1V8_1_20") (pintype "power_in"))
      (node (ref "U3") (pin "29") (pinfunction "VCCO1V8_0_29") (pintype "power_in"))
    )
    (net (code "247") (name "VDD_8") (class "Default")
      (node (ref "C28") (pin "1") (pinfunction "1_1") (pintype "passive"))
      (node (ref "C29") (pin "1") (pinfunction "1_1") (pintype "passive"))
      (node (ref "C30") (pin "1") (pinfunction "1_1") (pintype "passive"))
      (node (ref "C31") (pin "1") (pinfunction "1_1") (pintype "passive"))
      (node (ref "FB5") (pin "2") (pinfunction "2_2") (pintype "passive"))
      (node (ref "U4") (pin "16") (pinfunction "VDD_16") (pintype "power_in"))
      (node (ref "U4") (pin "20") (pinfunction "VCCO1V8_1_20") (pintype "power_in"))
      (node (ref "U4") (pin "29") (pinfunction "VCCO1V8_0_29") (pintype "power_in"))
    )
    (net (code "248") (name "VDD_9") (class "Default")
      (node (ref "C46") (pin "1") (pinfunction "1_1") (pintype "passive"))
      (node (ref "C47") (pin "1") (pinfunction "1_1") (pintype "passive"))
      (node (ref "C48") (pin "1") (pinfunction "1_1") (pintype "passive"))
      (node (ref "C49") (pin "1") (pinfunction "1_1") (pintype "passive"))
      (node (ref "FB8") (pin "2") (pinfunction "2_2") (pintype "passive"))
      (node (ref "U5") (pin "16") (pinfunction "VDD_16") (pintype "power_in"))
      (node (ref "U5") (pin "20") (pinfunction "VCCO1V8_1_20") (pintype "power_in"))
      (node (ref "U5") (pin "29") (pinfunction "VCCO1V8_0_29") (pintype "power_in"))
    )
    (net (code "249") (name "VOUT_A") (class "Default")
      (node (ref "C57") (pin "1") (pinfunction "1_1") (pintype "passive"))
      (node (ref "FB11") (pin "1") (pinfunction "1_1") (pintype "passive"))
      (node (ref "R17") (pin "2") (pinfunction "2_2") (pintype "passive"))
      (node (ref "U6") (pin "8") (pinfunction "VOUT_8") (pintype "output"))
    )
    (net (code "250") (name "VOUT_B") (class "Default")
      (node (ref "C59") (pin "1") (pinfunction "1_1") (pintype "passive"))
      (node (ref "FB12") (pin "1") (pinfunction "1_1") (pintype "passive"))
      (node (ref "R20") (pin "2") (pinfunction "2_2") (pintype "passive"))
      (node (ref "U7") (pin "8") (pinfunction "VOUT_8") (pintype "output"))
    )
    (net (code "251") (name "VSUP") (class "Default")
      (node (ref "C56") (pin "1") (pinfunction "1_1") (pintype "passive"))
      (node (ref "C58") (pin "1") (pinfunction "1_1") (pintype "passive"))
      (node (ref "JP1") (pin "2") (pinfunction "2_2") (pintype "passive"))
      (node (ref "R18") (pin "2") (pinfunction "2_2") (pintype "passive"))
      (node (ref "R21") (pin "2") (pinfunction "2_2") (pintype "passive"))
      (node (ref "U6") (pin "3") (pinfunction "VIN_3") (pintype "power_in"))
      (node (ref "U6") (pin "4") (pinfunction "VIN_4") (pintype "power_in"))
      (node (ref "U7") (pin "3") (pinfunction "VIN_3") (pintype "power_in"))
      (node (ref "U7") (pin "4") (pinfunction "VIN_4") (pintype "power_in"))
    )
    (net (code "252") (name "V_CLK") (class "Default")
      (node (ref "C1") (pin "1") (pinfunction "1_1") (pintype "passive"))
      (node (ref "FB1") (pin "2") (pinfunction "2_2") (pintype "passive"))
      (node (ref "U1") (pin "6") (pinfunction "VCC_6") (pintype "power_in"))
    )
    (net (code "253") (name "unconnected-(JTAG-Pad12)") (class "Default")
      (node (ref "JTAG") (pin "12") (pinfunction "12_12") (pintype "passive"))
    )
    (net (code "254") (name "unconnected-(JTAG-Pad14)") (class "Default")
      (node (ref "JTAG") (pin "14") (pinfunction "14_14") (pintype "passive"))
    )
    (net (code "255") (name "unconnected-(PCIE-NORTH-PWRGD-PadA11)") (class "Default")
      (node (ref "PCIE-NORTH") (pin "A11") (pinfunction "PWRGD_A11") (pintype "passive"))
    )
    (net (code "256") (name "unconnected-(PCIE-SOUTH-PWRGD-PadA11)") (class "Default")
      (node (ref "PCIE-SOUTH") (pin "A11") (pinfunction "PWRGD_A11") (pintype "passive"))
    )
    (net (code "257") (name "unconnected-(PCIE-SOUTH-SCL-PadB2)") (class "Default")
      (node (ref "PCIE-SOUTH") (pin "B2") (pinfunction "SCL_B2") (pintype "passive"))
    )
    (net (code "258") (name "unconnected-(PCIE-SOUTH-SDA-PadB1)") (class "Default")
      (node (ref "PCIE-SOUTH") (pin "B1") (pinfunction "SDA_B1") (pintype "passive"))
    )
    (net (code "259") (name "unconnected-(PCIE-SOUTH-V_I2C-PadB3)") (class "Default")
      (node (ref "PCIE-SOUTH") (pin "B3") (pinfunction "V_I2C_B3") (pintype "passive"))
    )
  )
)
